# SCH_Snoopy_2026-08-06.net
KiCad netlist of a schematic drawn in EasyEDA
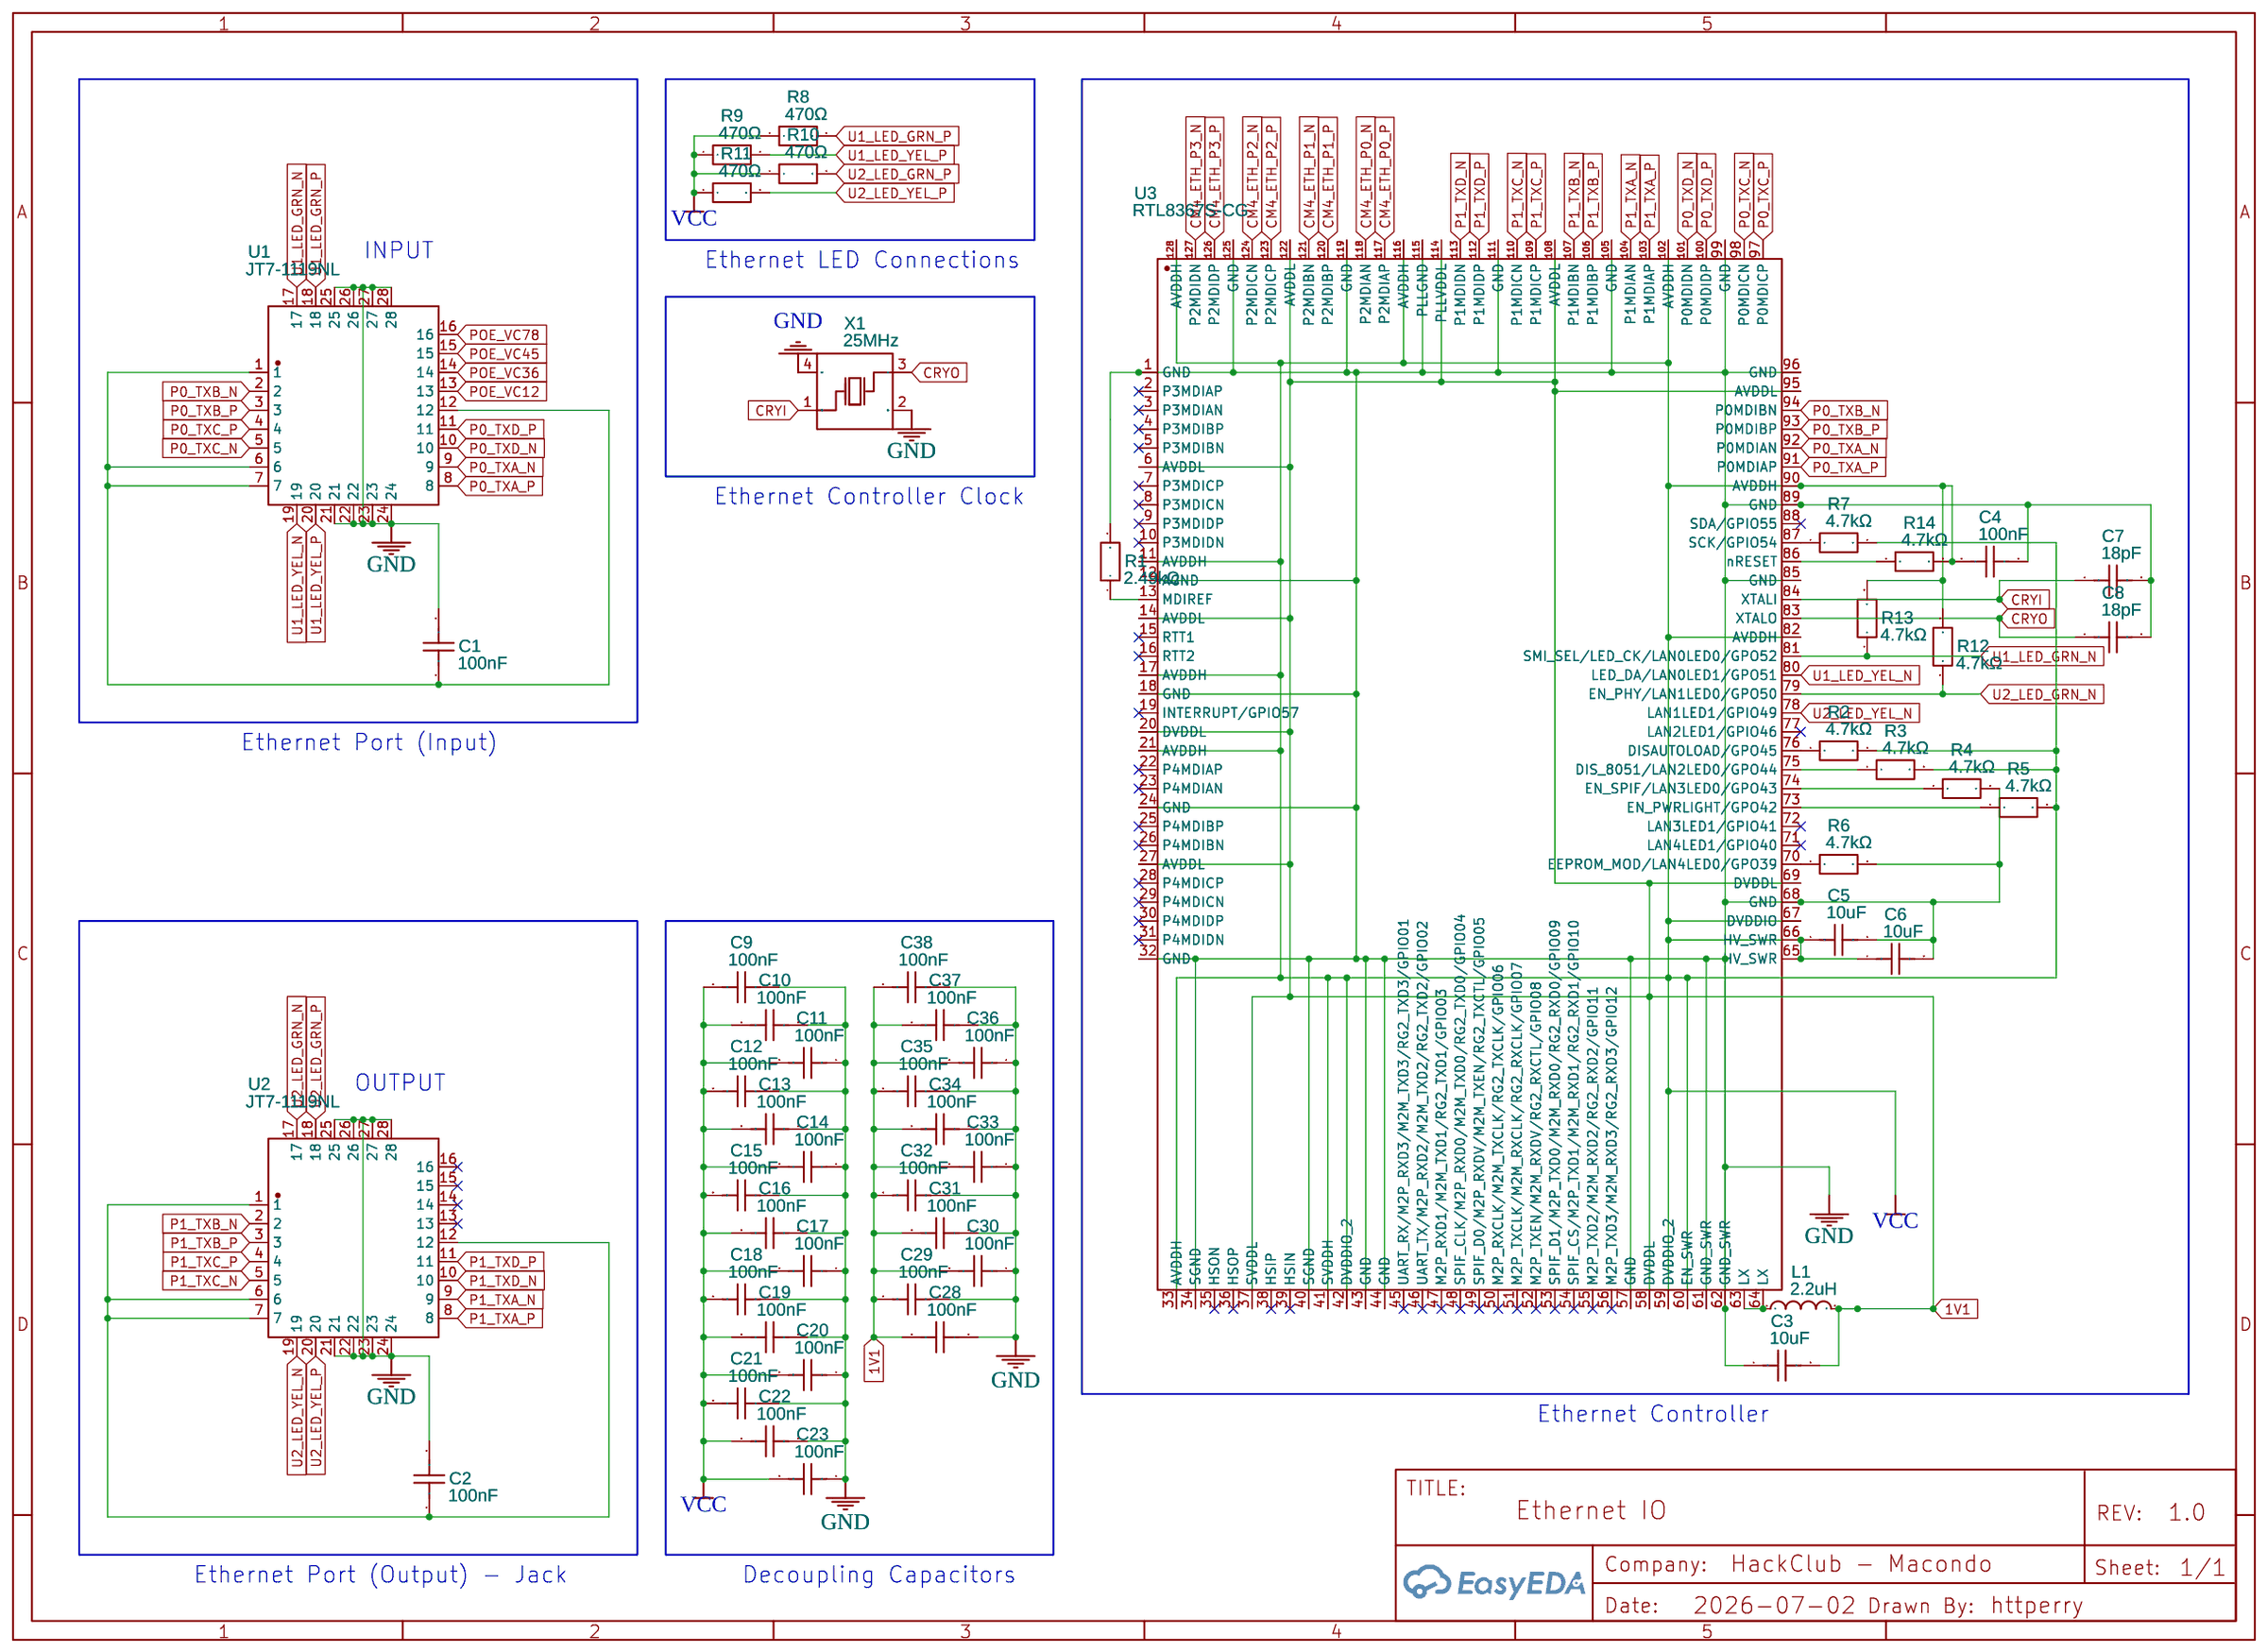
[diagram p0: Ethernet_IO]
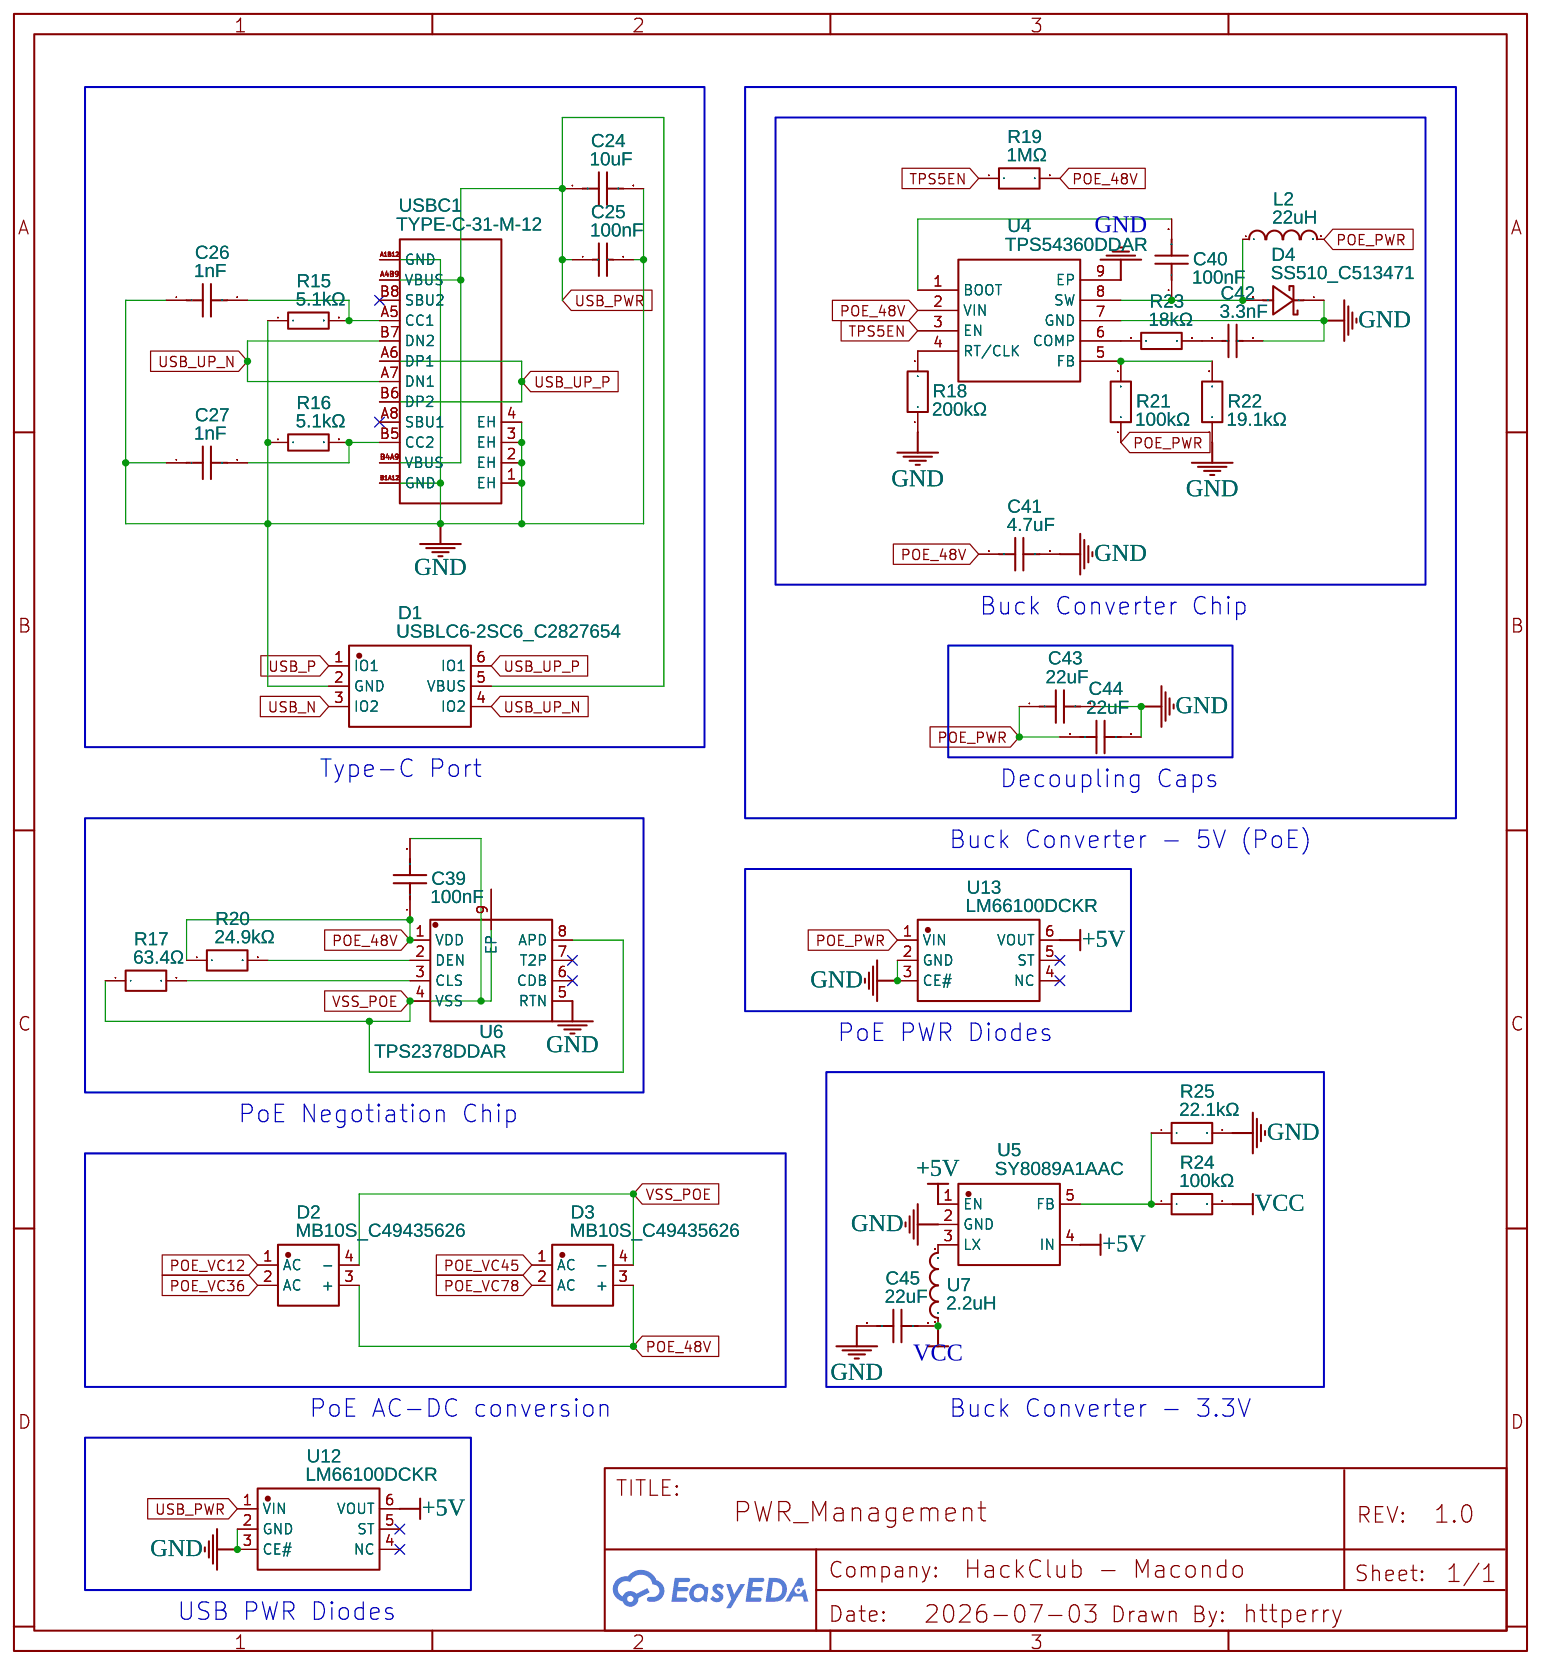
[diagram p1: PWR_Management]
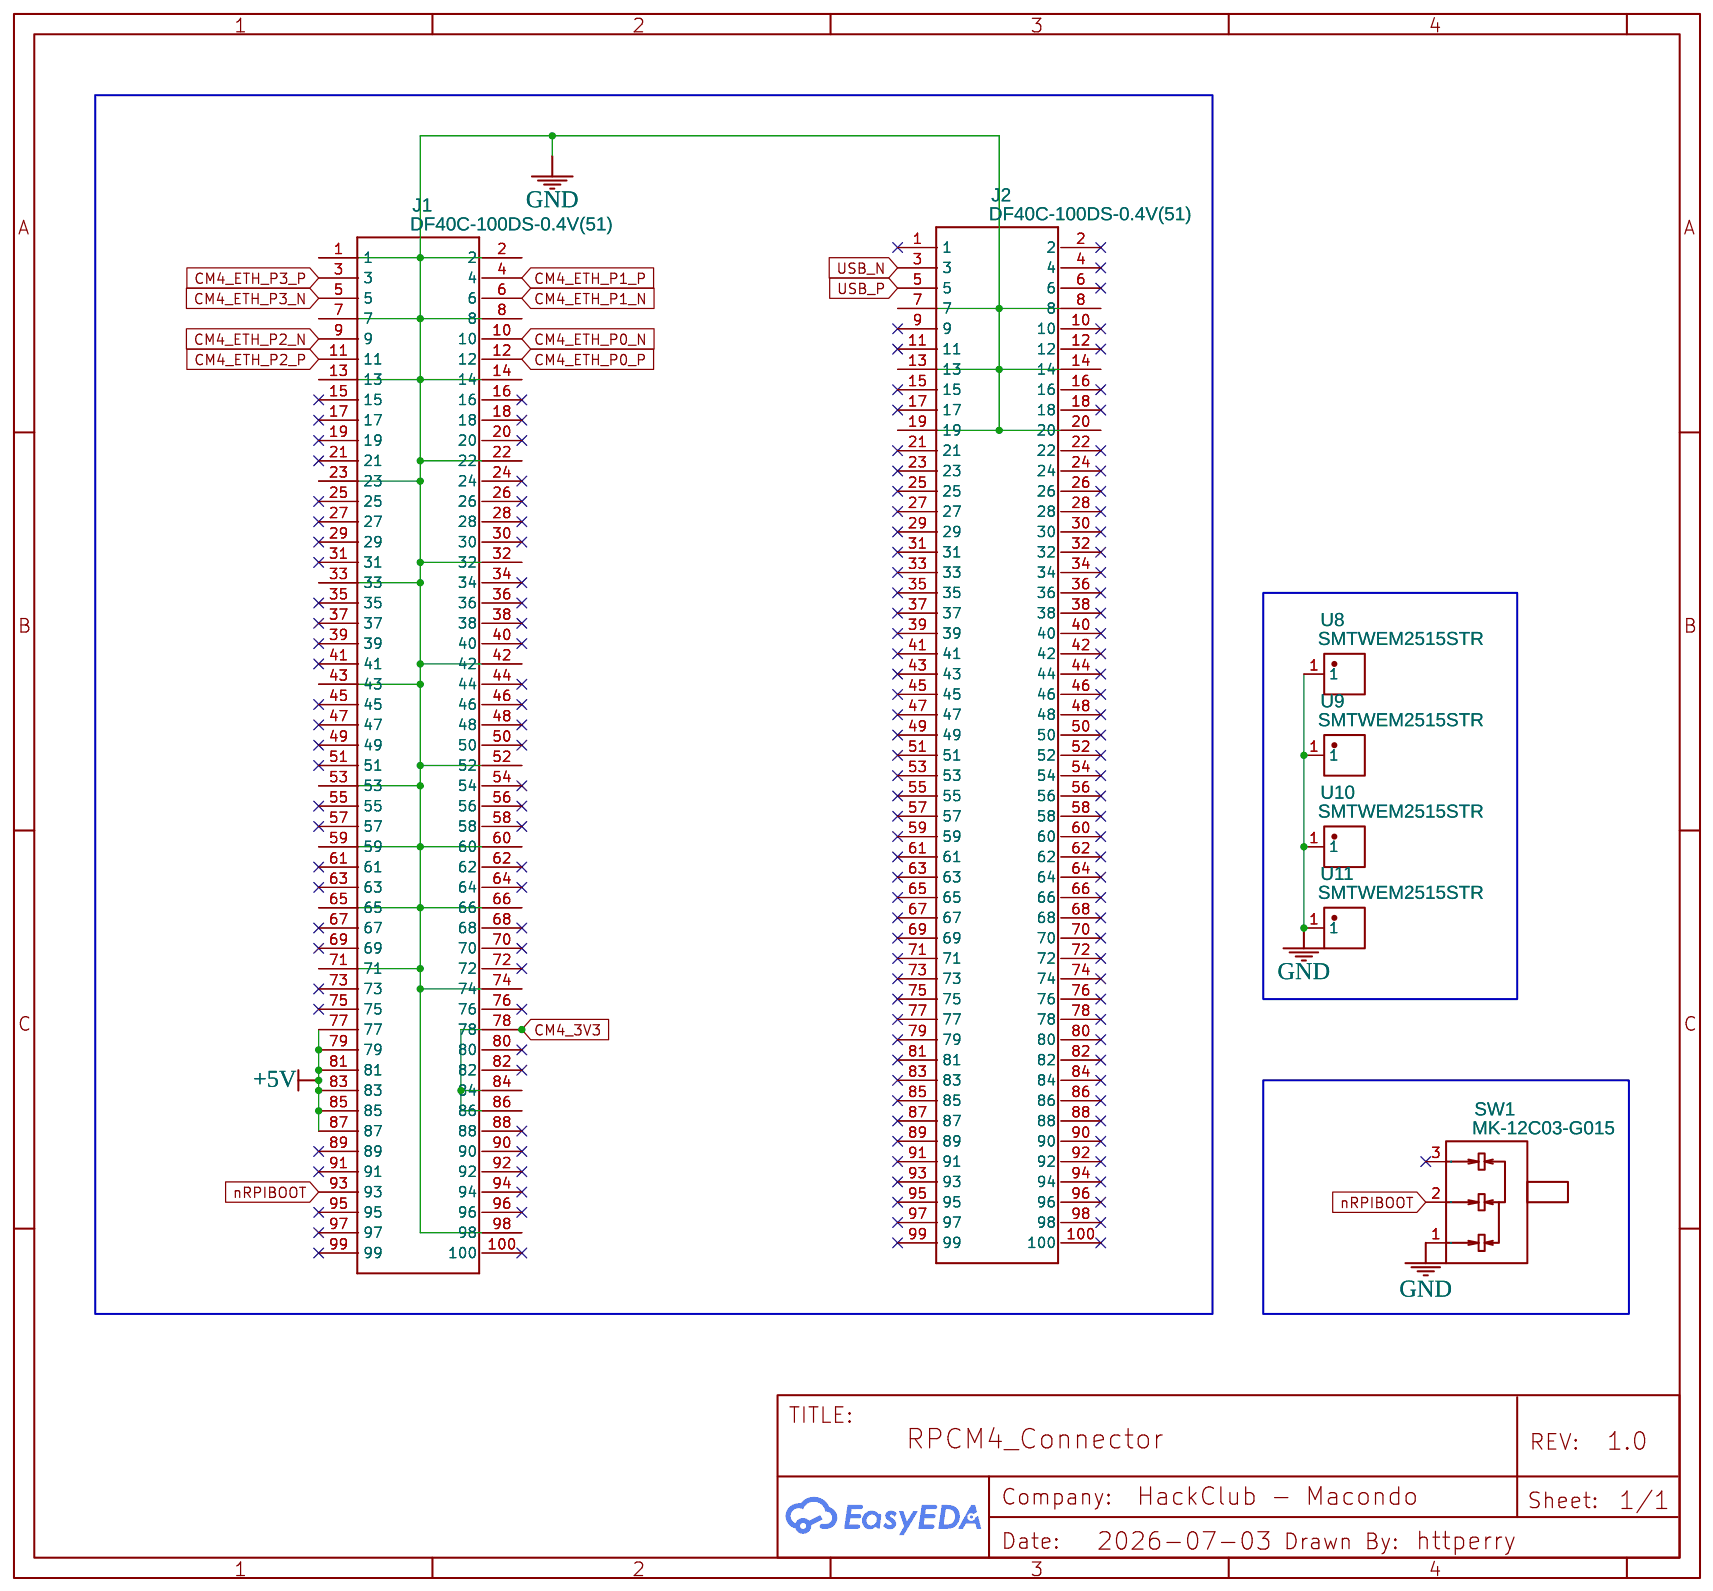
[diagram p2: RPCM4_Connector]

(export (version "E")
  (design (tool "Eeschema 10.0.6"))
  (components
    (comp (ref "C1")
      (value "100nF")
      (fields
        (field (name "Manufacturer Part") "AC0402KRX7R9BB104")
        (field (name "Manufacturer") "YAGEO(国巨)")
      )
      (libsource (lib "") (part "AC0402KRX7R9BB104_1"))
    )
    (comp (ref "C2")
      (value "100nF")
      (fields
        (field (name "Manufacturer Part") "AC0402KRX7R9BB104")
        (field (name "Manufacturer") "YAGEO(国巨)")
      )
      (libsource (lib "") (part "AC0402KRX7R9BB104_1"))
    )
    (comp (ref "C3")
      (value "10uF")
      (fields
        (field (name "Manufacturer Part") "HGC0603R5106M250NTHJ")
        (field (name "Manufacturer") "Chinocera(华瓷)")
      )
      (libsource (lib "") (part "HGC0603R5106M250NTHJ"))
    )
    (comp (ref "C4")
      (value "100nF")
      (fields
        (field (name "Manufacturer Part") "AC0402KRX7R9BB104")
        (field (name "Manufacturer") "YAGEO(国巨)")
      )
      (libsource (lib "") (part "AC0402KRX7R9BB104"))
    )
    (comp (ref "C5")
      (value "10uF")
      (fields
        (field (name "Manufacturer Part") "HGC0603R5106M250NTHJ")
        (field (name "Manufacturer") "Chinocera(华瓷)")
      )
      (libsource (lib "") (part "HGC0603R5106M250NTHJ"))
    )
    (comp (ref "C6")
      (value "10uF")
      (fields
        (field (name "Manufacturer Part") "HGC0603R5106M250NTHJ")
        (field (name "Manufacturer") "Chinocera(华瓷)")
      )
      (libsource (lib "") (part "HGC0603R5106M250NTHJ"))
    )
    (comp (ref "C7")
      (value "18pF")
      (fields
        (field (name "Manufacturer Part") "GRM1555C1H180JA01D")
        (field (name "Manufacturer") "muRata(村田)")
      )
      (libsource (lib "") (part "GRM1555C1H180JA01D"))
    )
    (comp (ref "C8")
      (value "18pF")
      (fields
        (field (name "Manufacturer Part") "GRM1555C1H180JA01D")
        (field (name "Manufacturer") "muRata(村田)")
      )
      (libsource (lib "") (part "GRM1555C1H180JA01D"))
    )
    (comp (ref "C9")
      (value "100nF")
      (fields
        (field (name "Manufacturer Part") "AC0402KRX7R9BB104")
        (field (name "Manufacturer") "YAGEO(国巨)")
      )
      (libsource (lib "") (part "AC0402KRX7R9BB104"))
    )
    (comp (ref "C10")
      (value "100nF")
      (fields
        (field (name "Manufacturer Part") "AC0402KRX7R9BB104")
        (field (name "Manufacturer") "YAGEO(国巨)")
      )
      (libsource (lib "") (part "AC0402KRX7R9BB104"))
    )
    (comp (ref "C11")
      (value "100nF")
      (fields
        (field (name "Manufacturer Part") "AC0402KRX7R9BB104")
        (field (name "Manufacturer") "YAGEO(国巨)")
      )
      (libsource (lib "") (part "AC0402KRX7R9BB104"))
    )
    (comp (ref "C12")
      (value "100nF")
      (fields
        (field (name "Manufacturer Part") "AC0402KRX7R9BB104")
        (field (name "Manufacturer") "YAGEO(国巨)")
      )
      (libsource (lib "") (part "AC0402KRX7R9BB104"))
    )
    (comp (ref "C13")
      (value "100nF")
      (fields
        (field (name "Manufacturer Part") "AC0402KRX7R9BB104")
        (field (name "Manufacturer") "YAGEO(国巨)")
      )
      (libsource (lib "") (part "AC0402KRX7R9BB104"))
    )
    (comp (ref "C14")
      (value "100nF")
      (fields
        (field (name "Manufacturer Part") "AC0402KRX7R9BB104")
        (field (name "Manufacturer") "YAGEO(国巨)")
      )
      (libsource (lib "") (part "AC0402KRX7R9BB104"))
    )
    (comp (ref "C15")
      (value "100nF")
      (fields
        (field (name "Manufacturer Part") "AC0402KRX7R9BB104")
        (field (name "Manufacturer") "YAGEO(国巨)")
      )
      (libsource (lib "") (part "AC0402KRX7R9BB104"))
    )
    (comp (ref "C16")
      (value "100nF")
      (fields
        (field (name "Manufacturer Part") "AC0402KRX7R9BB104")
        (field (name "Manufacturer") "YAGEO(国巨)")
      )
      (libsource (lib "") (part "AC0402KRX7R9BB104"))
    )
    (comp (ref "C17")
      (value "100nF")
      (fields
        (field (name "Manufacturer Part") "AC0402KRX7R9BB104")
        (field (name "Manufacturer") "YAGEO(国巨)")
      )
      (libsource (lib "") (part "AC0402KRX7R9BB104"))
    )
    (comp (ref "C18")
      (value "100nF")
      (fields
        (field (name "Manufacturer Part") "AC0402KRX7R9BB104")
        (field (name "Manufacturer") "YAGEO(国巨)")
      )
      (libsource (lib "") (part "AC0402KRX7R9BB104"))
    )
    (comp (ref "C19")
      (value "100nF")
      (fields
        (field (name "Manufacturer Part") "AC0402KRX7R9BB104")
        (field (name "Manufacturer") "YAGEO(国巨)")
      )
      (libsource (lib "") (part "AC0402KRX7R9BB104"))
    )
    (comp (ref "C20")
      (value "100nF")
      (fields
        (field (name "Manufacturer Part") "AC0402KRX7R9BB104")
        (field (name "Manufacturer") "YAGEO(国巨)")
      )
      (libsource (lib "") (part "AC0402KRX7R9BB104"))
    )
    (comp (ref "C21")
      (value "100nF")
      (fields
        (field (name "Manufacturer Part") "AC0402KRX7R9BB104")
        (field (name "Manufacturer") "YAGEO(国巨)")
      )
      (libsource (lib "") (part "AC0402KRX7R9BB104"))
    )
    (comp (ref "C22")
      (value "100nF")
      (fields
        (field (name "Manufacturer Part") "AC0402KRX7R9BB104")
        (field (name "Manufacturer") "YAGEO(国巨)")
      )
      (libsource (lib "") (part "AC0402KRX7R9BB104"))
    )
    (comp (ref "C23")
      (value "100nF")
      (fields
        (field (name "Manufacturer Part") "AC0402KRX7R9BB104")
        (field (name "Manufacturer") "YAGEO(国巨)")
      )
      (libsource (lib "") (part "AC0402KRX7R9BB104"))
    )
    (comp (ref "C28")
      (value "100nF")
      (fields
        (field (name "Manufacturer Part") "AC0402KRX7R9BB104")
        (field (name "Manufacturer") "YAGEO(国巨)")
      )
      (libsource (lib "") (part "AC0402KRX7R9BB104"))
    )
    (comp (ref "C29")
      (value "100nF")
      (fields
        (field (name "Manufacturer Part") "AC0402KRX7R9BB104")
        (field (name "Manufacturer") "YAGEO(国巨)")
      )
      (libsource (lib "") (part "AC0402KRX7R9BB104"))
    )
    (comp (ref "C30")
      (value "100nF")
      (fields
        (field (name "Manufacturer Part") "AC0402KRX7R9BB104")
        (field (name "Manufacturer") "YAGEO(国巨)")
      )
      (libsource (lib "") (part "AC0402KRX7R9BB104"))
    )
    (comp (ref "C31")
      (value "100nF")
      (fields
        (field (name "Manufacturer Part") "AC0402KRX7R9BB104")
        (field (name "Manufacturer") "YAGEO(国巨)")
      )
      (libsource (lib "") (part "AC0402KRX7R9BB104"))
    )
    (comp (ref "C32")
      (value "100nF")
      (fields
        (field (name "Manufacturer Part") "AC0402KRX7R9BB104")
        (field (name "Manufacturer") "YAGEO(国巨)")
      )
      (libsource (lib "") (part "AC0402KRX7R9BB104"))
    )
    (comp (ref "C33")
      (value "100nF")
      (fields
        (field (name "Manufacturer Part") "AC0402KRX7R9BB104")
        (field (name "Manufacturer") "YAGEO(国巨)")
      )
      (libsource (lib "") (part "AC0402KRX7R9BB104"))
    )
    (comp (ref "C34")
      (value "100nF")
      (fields
        (field (name "Manufacturer Part") "AC0402KRX7R9BB104")
        (field (name "Manufacturer") "YAGEO(国巨)")
      )
      (libsource (lib "") (part "AC0402KRX7R9BB104"))
    )
    (comp (ref "C35")
      (value "100nF")
      (fields
        (field (name "Manufacturer Part") "AC0402KRX7R9BB104")
        (field (name "Manufacturer") "YAGEO(国巨)")
      )
      (libsource (lib "") (part "AC0402KRX7R9BB104"))
    )
    (comp (ref "C36")
      (value "100nF")
      (fields
        (field (name "Manufacturer Part") "AC0402KRX7R9BB104")
        (field (name "Manufacturer") "YAGEO(国巨)")
      )
      (libsource (lib "") (part "AC0402KRX7R9BB104"))
    )
    (comp (ref "C37")
      (value "100nF")
      (fields
        (field (name "Manufacturer Part") "AC0402KRX7R9BB104")
        (field (name "Manufacturer") "YAGEO(国巨)")
      )
      (libsource (lib "") (part "AC0402KRX7R9BB104"))
    )
    (comp (ref "C38")
      (value "100nF")
      (fields
        (field (name "Manufacturer Part") "AC0402KRX7R9BB104")
        (field (name "Manufacturer") "YAGEO(国巨)")
      )
      (libsource (lib "") (part "AC0402KRX7R9BB104"))
    )
    (comp (ref "L1")
      (value "2.2uH")
      (fields (field (name "Manufacturer Part") "ZEMS160865-2R2M") (field (name "Manufacturer") "ZE(增益)"))
      (libsource (lib "") (part "ZEMS160865-2R2M"))
    )
    (comp (ref "R1")
      (value "2.49kΩ")
      (fields (field (name "Manufacturer Part") "FRC0402F2491TS") (field (name "Manufacturer") "FOJAN(富捷)"))
      (libsource (lib "") (part "FRC0402F2491TS"))
    )
    (comp (ref "R2")
      (value "4.7kΩ")
      (fields
        (field (name "Manufacturer Part") "CRCW04024K70FKED")
        (field (name "Manufacturer") "VISHAY(威世)")
      )
      (libsource (lib "") (part "CRCW04024K70FKED_1"))
    )
    (comp (ref "R3")
      (value "4.7kΩ")
      (fields
        (field (name "Manufacturer Part") "CRCW04024K70FKED")
        (field (name "Manufacturer") "VISHAY(威世)")
      )
      (libsource (lib "") (part "CRCW04024K70FKED_1"))
    )
    (comp (ref "R4")
      (value "4.7kΩ")
      (fields
        (field (name "Manufacturer Part") "CRCW04024K70FKED")
        (field (name "Manufacturer") "VISHAY(威世)")
      )
      (libsource (lib "") (part "CRCW04024K70FKED_1"))
    )
    (comp (ref "R5")
      (value "4.7kΩ")
      (fields
        (field (name "Manufacturer Part") "CRCW04024K70FKED")
        (field (name "Manufacturer") "VISHAY(威世)")
      )
      (libsource (lib "") (part "CRCW04024K70FKED_1"))
    )
    (comp (ref "R6")
      (value "4.7kΩ")
      (fields
        (field (name "Manufacturer Part") "CRCW04024K70FKED")
        (field (name "Manufacturer") "VISHAY(威世)")
      )
      (libsource (lib "") (part "CRCW04024K70FKED_1"))
    )
    (comp (ref "R7")
      (value "4.7kΩ")
      (fields
        (field (name "Manufacturer Part") "CRCW04024K70FKED")
        (field (name "Manufacturer") "VISHAY(威世)")
      )
      (libsource (lib "") (part "CRCW04024K70FKED_1"))
    )
    (comp (ref "R8")
      (value "470Ω")
      (fields (field (name "Manufacturer Part") "FRC0402F4700TS") (field (name "Manufacturer") "FOJAN(富捷)"))
      (libsource (lib "") (part "FRC0402F4700TS"))
    )
    (comp (ref "R9")
      (value "470Ω")
      (fields (field (name "Manufacturer Part") "FRC0402F4700TS") (field (name "Manufacturer") "FOJAN(富捷)"))
      (libsource (lib "") (part "FRC0402F4700TS"))
    )
    (comp (ref "R10")
      (value "470Ω")
      (fields (field (name "Manufacturer Part") "FRC0402F4700TS") (field (name "Manufacturer") "FOJAN(富捷)"))
      (libsource (lib "") (part "FRC0402F4700TS"))
    )
    (comp (ref "R11")
      (value "470Ω")
      (fields (field (name "Manufacturer Part") "FRC0402F4700TS") (field (name "Manufacturer") "FOJAN(富捷)"))
      (libsource (lib "") (part "FRC0402F4700TS"))
    )
    (comp (ref "R12")
      (value "4.7kΩ")
      (fields
        (field (name "Manufacturer Part") "CRCW04024K70FKED")
        (field (name "Manufacturer") "VISHAY(威世)")
      )
      (libsource (lib "") (part "CRCW04024K70FKED"))
    )
    (comp (ref "R13")
      (value "4.7kΩ")
      (fields
        (field (name "Manufacturer Part") "CRCW04024K70FKED")
        (field (name "Manufacturer") "VISHAY(威世)")
      )
      (libsource (lib "") (part "CRCW04024K70FKED"))
    )
    (comp (ref "R14")
      (value "4.7kΩ")
      (fields
        (field (name "Manufacturer Part") "CRCW04024K70FKED")
        (field (name "Manufacturer") "VISHAY(威世)")
      )
      (libsource (lib "") (part "CRCW04024K70FKED_1"))
    )
    (comp (ref "U1")
      (value "JT7-1119NL")
      (fields (field (name "Manufacturer") "PULSE(普思)"))
      (libsource (lib "") (part "JT7-1119NL"))
    )
    (comp (ref "U2")
      (value "JT7-1119NL")
      (fields (field (name "Manufacturer") "PULSE(普思)"))
      (libsource (lib "") (part "JT7-1119NL"))
    )
    (comp (ref "U3")
      (value "RTL8367S-CG")
      (fields (field (name "Manufacturer") "REALTEK(瑞昱)"))
      (libsource (lib "") (part "RTL8367S-CG"))
    )
    (comp (ref "X1")
      (value "25MHz")
      (fields (field (name "Manufacturer Part") "TAXM25M4RLBCCT2T") (field (name "Manufacturer") "YJX(雅晶鑫)"))
      (libsource (lib "") (part "SMD-3225_4P25MHZ20PF10PPM-40&#126;+85℃"))
    )
    (comp (ref "C24")
      (value "10uF")
      (fields
        (field (name "Manufacturer Part") "HGC0603R5106M250NTHJ")
        (field (name "Manufacturer") "Chinocera(华瓷)")
      )
      (libsource (lib "") (part "HGC0603R5106M250NTHJ"))
    )
    (comp (ref "C25")
      (value "100nF")
      (fields
        (field (name "Manufacturer Part") "CC0402KRX5R8BB104")
        (field (name "Manufacturer") "YAGEO(国巨)")
      )
      (libsource (lib "") (part "CC0402KRX5R8BB104"))
    )
    (comp (ref "C26")
      (value "1nF")
      (fields
        (field (name "Manufacturer Part") "CC0402KRX7R8BB102")
        (field (name "Manufacturer") "YAGEO(国巨)")
      )
      (libsource (lib "") (part "CC0402KRX7R8BB102"))
    )
    (comp (ref "C27")
      (value "1nF")
      (fields
        (field (name "Manufacturer Part") "CC0402KRX7R8BB102")
        (field (name "Manufacturer") "YAGEO(国巨)")
      )
      (libsource (lib "") (part "CC0402KRX7R8BB102"))
    )
    (comp (ref "C39")
      (value "100nF")
      (fields
        (field (name "Manufacturer Part") "GCJ188R72A104KA01D")
        (field (name "Manufacturer") "muRata(村田)")
      )
      (libsource (lib "") (part "GCJ188R72A104KA01D"))
    )
    (comp (ref "C40")
      (value "100nF")
      (fields
        (field (name "Manufacturer Part") "GCJ188R72A104KA01D")
        (field (name "Manufacturer") "muRata(村田)")
      )
      (libsource (lib "") (part "GCJ188R72A104KA01D"))
    )
    (comp (ref "C41")
      (value "4.7uF")
      (fields
        (field (name "Manufacturer Part") "GRM31CC72A475KE11L")
        (field (name "Manufacturer") "muRata(村田)")
      )
      (libsource (lib "") (part "GRM31CC72A475KE11L"))
    )
    (comp (ref "C42")
      (value "3.3nF")
      (fields
        (field (name "Manufacturer Part") "CC0402KRX7R9BB332")
        (field (name "Manufacturer") "YAGEO(国巨)")
      )
      (libsource (lib "") (part "CC0402KRX7R9BB332"))
    )
    (comp (ref "C43")
      (value "22uF")
      (fields
        (field (name "Manufacturer Part") "CL10A226MP8NUNE")
        (field (name "Manufacturer") "SAMSUNG(三星)")
      )
      (libsource (lib "") (part "CL10A226MP8NUNE"))
    )
    (comp (ref "C44")
      (value "22uF")
      (fields
        (field (name "Manufacturer Part") "CL10A226MP8NUNE")
        (field (name "Manufacturer") "SAMSUNG(三星)")
      )
      (libsource (lib "") (part "CL10A226MP8NUNE"))
    )
    (comp (ref "C45")
      (value "22uF")
      (fields
        (field (name "Manufacturer Part") "HGC0402R5226M100NTEJ")
        (field (name "Manufacturer") "Chinocera(华瓷)")
      )
      (libsource (lib "") (part "HGC0402R5226M100NTEJ"))
    )
    (comp (ref "D1")
      (value "USBLC6-2SC6_C2827654")
      (fields
        (field (name "Manufacturer Part") "USBLC6-2SC6")
        (field (name "Manufacturer") "TECH PUBLIC(台舟)")
      )
      (libsource (lib "") (part "USBLC6-2SC6_C2827654"))
    )
    (comp (ref "D2")
      (value "MB10S_C49435626")
      (fields (field (name "Manufacturer Part") "MB10S") (field (name "Manufacturer") "Huixin(慧芯)"))
      (libsource (lib "") (part "MB10S_C49435626"))
    )
    (comp (ref "D3")
      (value "MB10S_C49435626")
      (fields (field (name "Manufacturer Part") "MB10S") (field (name "Manufacturer") "Huixin(慧芯)"))
      (libsource (lib "") (part "MB10S_C49435626"))
    )
    (comp (ref "D4")
      (value "SS510_C513471")
      (fields (field (name "Manufacturer Part") "SS510") (field (name "Manufacturer") "Slkor(萨科微)"))
      (libsource (lib "") (part "SS510_C513471"))
    )
    (comp (ref "L2")
      (value "22uH")
      (fields
        (field (name "Manufacturer Part") "YSPI0630A-220M")
        (field (name "Manufacturer") "YJYCOIN(益嘉源)")
      )
      (libsource (lib "") (part "YSPI0630A-220M"))
    )
    (comp (ref "R15")
      (value "5.1kΩ")
      (fields (field (name "Manufacturer Part") "RMC06035.1K5%N") (field (name "Manufacturer") "Tyohm(幸亚电阻)"))
      (libsource (lib "") (part "RMC06035.1K5%N"))
    )
    (comp (ref "R16")
      (value "5.1kΩ")
      (fields (field (name "Manufacturer Part") "RMC06035.1K5%N") (field (name "Manufacturer") "Tyohm(幸亚电阻)"))
      (libsource (lib "") (part "RMC06035.1K5%N"))
    )
    (comp (ref "R17")
      (value "63.4Ω")
      (fields (field (name "Manufacturer Part") "PTFR0603B63R4P9") (field (name "Manufacturer") "RESI(开步睿思)"))
      (libsource (lib "") (part "PTFR0603B63R4P9"))
    )
    (comp (ref "R18")
      (value "200kΩ")
      (fields (field (name "Manufacturer Part") "ARG02BTC2003") (field (name "Manufacturer") "Viking(光颉)"))
      (libsource (lib "") (part "ARG02BTC2003"))
    )
    (comp (ref "R19")
      (value "1MΩ")
      (fields (field (name "Manufacturer Part") "AR05BTC1004") (field (name "Manufacturer") "Viking(光颉)"))
      (libsource (lib "") (part "AR05BTC1004"))
    )
    (comp (ref "R20")
      (value "24.9kΩ")
      (fields (field (name "Manufacturer Part") "PTFR0603B24K9N9") (field (name "Manufacturer") "RESI(开步睿思)"))
      (libsource (lib "") (part "PTFR0603B24K9N9"))
    )
    (comp (ref "R21")
      (value "100kΩ")
      (fields (field (name "Manufacturer Part") "RT0402BRD07100KL") (field (name "Manufacturer") "YAGEO(国巨)"))
      (libsource (lib "") (part "RT0402BRD07100KL_1"))
    )
    (comp (ref "R22")
      (value "19.1kΩ")
      (fields (field (name "Manufacturer Part") "FRC0402F1912TS") (field (name "Manufacturer") "FOJAN(富捷)"))
      (libsource (lib "") (part "FRC0402F1912TS"))
    )
    (comp (ref "R23")
      (value "18kΩ")
      (fields (field (name "Manufacturer Part") "AECR0402F18K0K9") (field (name "Manufacturer") "RESI(开步睿思)"))
      (libsource (lib "") (part "AECR0402F18K0K9"))
    )
    (comp (ref "R24")
      (value "100kΩ")
      (fields (field (name "Manufacturer Part") "RT0402BRD07100KL") (field (name "Manufacturer") "YAGEO(国巨)"))
      (libsource (lib "") (part "RT0402BRD07100KL"))
    )
    (comp (ref "R25")
      (value "22.1kΩ")
      (fields
        (field (name "Manufacturer Part") "CRCW040222K1FKED")
        (field (name "Manufacturer") "VISHAY(威世)")
      )
      (libsource (lib "") (part "CRCW040222K1FKED"))
    )
    (comp (ref "U4")
      (value "TPS54360DDAR")
      (fields (field (name "Manufacturer") "TI(德州仪器)"))
      (libsource (lib "") (part "TPS54360DDAR"))
    )
    (comp (ref "U5")
      (value "SY8089A1AAC")
      (fields (field (name "Manufacturer") "Silergy(矽力杰)"))
      (libsource (lib "") (part "SY8089A1AAC"))
    )
    (comp (ref "U6")
      (value "TPS2378DDAR")
      (fields (field (name "Manufacturer") "TI(德州仪器)"))
      (libsource (lib "") (part "TPS2378DDAR"))
    )
    (comp (ref "U7")
      (value "2.2uH")
      (fields
        (field (name "Manufacturer Part") "FTC201610S2R2MBCA")
        (field (name "Manufacturer") "cjiang(长江微电)")
      )
      (libsource (lib "") (part "FTC201610S2R2MBCA"))
    )
    (comp (ref "U12")
      (value "LM66100DCKR")
      (fields (field (name "Manufacturer") "TI(德州仪器)"))
      (libsource (lib "") (part "LM66100DCKR"))
    )
    (comp (ref "U13")
      (value "LM66100DCKR")
      (fields (field (name "Manufacturer") "TI(德州仪器)"))
      (libsource (lib "") (part "LM66100DCKR"))
    )
    (comp (ref "USBC1")
      (value "TYPE-C-31-M-12")
      (fields (field (name "Manufacturer") "韩国韩荣"))
      (libsource (lib "") (part "TYPE-C-31-M-12"))
    )
    (comp (ref "J1")
      (value "DF40C-100DS-0.4V(51)")
      (fields (field (name "Manufacturer") "HRS(广濑)"))
      (libsource (lib "") (part "DF40C-100DS-0.4V(51)"))
    )
    (comp (ref "J2")
      (value "DF40C-100DS-0.4V(51)")
      (fields (field (name "Manufacturer") "HRS(广濑)"))
      (libsource (lib "") (part "DF40C-100DS-0.4V(51)"))
    )
    (comp (ref "SW1")
      (value "MK-12C03-G015")
      (fields (field (name "Manufacturer") "G-Switch(品赞)"))
      (libsource (lib "") (part "MK-12C03-G015"))
    )
    (comp (ref "U8")
      (value "SMTWEM2515STR")
      (fields (field (name "Manufacturer") "YIYUAN(怡远)"))
      (libsource (lib "") (part "SMTWEM2515STR"))
    )
    (comp (ref "U9")
      (value "SMTWEM2515STR")
      (fields (field (name "Manufacturer") "YIYUAN(怡远)"))
      (libsource (lib "") (part "SMTWEM2515STR"))
    )
    (comp (ref "U10")
      (value "SMTWEM2515STR")
      (fields (field (name "Manufacturer") "YIYUAN(怡远)"))
      (libsource (lib "") (part "SMTWEM2515STR"))
    )
    (comp (ref "U11")
      (value "SMTWEM2515STR")
      (fields (field (name "Manufacturer") "YIYUAN(怡远)"))
      (libsource (lib "") (part "SMTWEM2515STR"))
    )
  )
  (nets
    (net (code "1") (name "+5V") (class "Default")
      (node (ref "J1") (pin "77") (pinfunction "77_77") (pintype "bidirectional"))
      (node (ref "J1") (pin "79") (pinfunction "79_79") (pintype "bidirectional"))
      (node (ref "J1") (pin "81") (pinfunction "81_81") (pintype "bidirectional"))
      (node (ref "J1") (pin "83") (pinfunction "83_83") (pintype "bidirectional"))
      (node (ref "J1") (pin "85") (pinfunction "85_85") (pintype "bidirectional"))
      (node (ref "J1") (pin "87") (pinfunction "87_87") (pintype "bidirectional"))
      (node (ref "U12") (pin "6") (pinfunction "VOUT_6") (pintype "unspecified"))
      (node (ref "U13") (pin "6") (pinfunction "VOUT_6") (pintype "unspecified"))
      (node (ref "U5") (pin "1") (pinfunction "EN_1") (pintype "unspecified"))
      (node (ref "U5") (pin "4") (pinfunction "IN_4") (pintype "unspecified"))
    )
    (net (code "2") (name "1V1") (class "Default")
      (node (ref "C28") (pin "2") (pinfunction "2_2") (pintype "unspecified"))
      (node (ref "C29") (pin "2") (pinfunction "2_2") (pintype "unspecified"))
      (node (ref "C3") (pin "2") (pinfunction "2_2") (pintype "unspecified"))
      (node (ref "C30") (pin "2") (pinfunction "2_2") (pintype "unspecified"))
      (node (ref "C31") (pin "2") (pinfunction "2_2") (pintype "unspecified"))
      (node (ref "C32") (pin "2") (pinfunction "2_2") (pintype "unspecified"))
      (node (ref "C33") (pin "2") (pinfunction "2_2") (pintype "unspecified"))
      (node (ref "C34") (pin "2") (pinfunction "2_2") (pintype "unspecified"))
      (node (ref "C35") (pin "2") (pinfunction "2_2") (pintype "unspecified"))
      (node (ref "C36") (pin "2") (pinfunction "2_2") (pintype "unspecified"))
      (node (ref "C37") (pin "2") (pinfunction "2_2") (pintype "unspecified"))
      (node (ref "C38") (pin "2") (pinfunction "2_2") (pintype "unspecified"))
      (node (ref "L1") (pin "2") (pinfunction "2_2") (pintype "unspecified"))
      (node (ref "U3") (pin "108") (pinfunction "AVDDL_108") (pintype "unspecified"))
      (node (ref "U3") (pin "114") (pinfunction "PLLVDDL_114") (pintype "unspecified"))
      (node (ref "U3") (pin "122") (pinfunction "AVDDL_122") (pintype "unspecified"))
      (node (ref "U3") (pin "14") (pinfunction "AVDDL_14") (pintype "unspecified"))
      (node (ref "U3") (pin "20") (pinfunction "DVDDL_20") (pintype "unspecified"))
      (node (ref "U3") (pin "27") (pinfunction "AVDDL_27") (pintype "unspecified"))
      (node (ref "U3") (pin "37") (pinfunction "SVDDL_37") (pintype "unspecified"))
      (node (ref "U3") (pin "58") (pinfunction "DVDDL_58") (pintype "unspecified"))
      (node (ref "U3") (pin "6") (pinfunction "AVDDL_6") (pintype "unspecified"))
      (node (ref "U3") (pin "69") (pinfunction "DVDDL_69") (pintype "unspecified"))
      (node (ref "U3") (pin "95") (pinfunction "AVDDL_95") (pintype "unspecified"))
    )
    (net (code "3") (name "CM4_3V3") (class "Default")
      (node (ref "J1") (pin "78") (pinfunction "78_78") (pintype "bidirectional"))
      (node (ref "J1") (pin "84") (pinfunction "84_84") (pintype "bidirectional"))
      (node (ref "J1") (pin "86") (pinfunction "86_86") (pintype "bidirectional"))
    )
    (net (code "4") (name "CM4_ETH_P0_N") (class "Default")
      (node (ref "J1") (pin "10") (pinfunction "10_10") (pintype "bidirectional"))
      (node (ref "U3") (pin "118") (pinfunction "P2MDIAN_118") (pintype "unspecified"))
    )
    (net (code "5") (name "CM4_ETH_P0_P") (class "Default")
      (node (ref "J1") (pin "12") (pinfunction "12_12") (pintype "bidirectional"))
      (node (ref "U3") (pin "117") (pinfunction "P2MDIAP_117") (pintype "unspecified"))
    )
    (net (code "6") (name "CM4_ETH_P1_N") (class "Default")
      (node (ref "J1") (pin "6") (pinfunction "6_6") (pintype "bidirectional"))
      (node (ref "U3") (pin "121") (pinfunction "P2MDIBN_121") (pintype "unspecified"))
    )
    (net (code "7") (name "CM4_ETH_P1_P") (class "Default")
      (node (ref "J1") (pin "4") (pinfunction "4_4") (pintype "bidirectional"))
      (node (ref "U3") (pin "120") (pinfunction "P2MDIBP_120") (pintype "unspecified"))
    )
    (net (code "8") (name "CM4_ETH_P2_N") (class "Default")
      (node (ref "J1") (pin "9") (pinfunction "9_9") (pintype "bidirectional"))
      (node (ref "U3") (pin "124") (pinfunction "P2MDICN_124") (pintype "unspecified"))
    )
    (net (code "9") (name "CM4_ETH_P2_P") (class "Default")
      (node (ref "J1") (pin "11") (pinfunction "11_11") (pintype "bidirectional"))
      (node (ref "U3") (pin "123") (pinfunction "P2MDICP_123") (pintype "unspecified"))
    )
    (net (code "10") (name "CM4_ETH_P3_N") (class "Default")
      (node (ref "J1") (pin "5") (pinfunction "5_5") (pintype "bidirectional"))
      (node (ref "U3") (pin "127") (pinfunction "P2MDIDN_127") (pintype "unspecified"))
    )
    (net (code "11") (name "CM4_ETH_P3_P") (class "Default")
      (node (ref "J1") (pin "3") (pinfunction "3_3") (pintype "bidirectional"))
      (node (ref "U3") (pin "126") (pinfunction "P2MDIDP_126") (pintype "unspecified"))
    )
    (net (code "12") (name "CRYI") (class "Default")
      (node (ref "C7") (pin "1") (pinfunction "1_1") (pintype "unspecified"))
      (node (ref "U3") (pin "84") (pinfunction "XTALI_84") (pintype "unspecified"))
      (node (ref "X1") (pin "1") (pinfunction "OSC1_1") (pintype "unspecified"))
    )
    (net (code "13") (name "CRYO") (class "Default")
      (node (ref "C8") (pin "1") (pinfunction "1_1") (pintype "unspecified"))
      (node (ref "U3") (pin "83") (pinfunction "XTALO_83") (pintype "unspecified"))
      (node (ref "X1") (pin "3") (pinfunction "OSC2_3") (pintype "unspecified"))
    )
    (net (code "14") (name "GND") (class "Default")
      (node (ref "C1") (pin "2") (pinfunction "2_2") (pintype "unspecified"))
      (node (ref "C10") (pin "1") (pinfunction "1_1") (pintype "unspecified"))
      (node (ref "C11") (pin "1") (pinfunction "1_1") (pintype "unspecified"))
      (node (ref "C12") (pin "1") (pinfunction "1_1") (pintype "unspecified"))
      (node (ref "C13") (pin "1") (pinfunction "1_1") (pintype "unspecified"))
      (node (ref "C14") (pin "1") (pinfunction "1_1") (pintype "unspecified"))
      (node (ref "C15") (pin "1") (pinfunction "1_1") (pintype "unspecified"))
      (node (ref "C16") (pin "1") (pinfunction "1_1") (pintype "unspecified"))
      (node (ref "C17") (pin "1") (pinfunction "1_1") (pintype "unspecified"))
      (node (ref "C18") (pin "1") (pinfunction "1_1") (pintype "unspecified"))
      (node (ref "C19") (pin "1") (pinfunction "1_1") (pintype "unspecified"))
      (node (ref "C2") (pin "2") (pinfunction "2_2") (pintype "unspecified"))
      (node (ref "C20") (pin "1") (pinfunction "1_1") (pintype "unspecified"))
      (node (ref "C21") (pin "1") (pinfunction "1_1") (pintype "unspecified"))
      (node (ref "C22") (pin "1") (pinfunction "1_1") (pintype "unspecified"))
      (node (ref "C23") (pin "1") (pinfunction "1_1") (pintype "unspecified"))
      (node (ref "C24") (pin "2") (pinfunction "2_2") (pintype "unspecified"))
      (node (ref "C25") (pin "2") (pinfunction "2_2") (pintype "input"))
      (node (ref "C26") (pin "1") (pinfunction "1_1") (pintype "unspecified"))
      (node (ref "C27") (pin "1") (pinfunction "1_1") (pintype "unspecified"))
      (node (ref "C28") (pin "1") (pinfunction "1_1") (pintype "unspecified"))
      (node (ref "C29") (pin "1") (pinfunction "1_1") (pintype "unspecified"))
      (node (ref "C3") (pin "1") (pinfunction "1_1") (pintype "unspecified"))
      (node (ref "C30") (pin "1") (pinfunction "1_1") (pintype "unspecified"))
      (node (ref "C31") (pin "1") (pinfunction "1_1") (pintype "unspecified"))
      (node (ref "C32") (pin "1") (pinfunction "1_1") (pintype "unspecified"))
      (node (ref "C33") (pin "1") (pinfunction "1_1") (pintype "unspecified"))
      (node (ref "C34") (pin "1") (pinfunction "1_1") (pintype "unspecified"))
      (node (ref "C35") (pin "1") (pinfunction "1_1") (pintype "unspecified"))
      (node (ref "C36") (pin "1") (pinfunction "1_1") (pintype "unspecified"))
      (node (ref "C37") (pin "1") (pinfunction "1_1") (pintype "unspecified"))
      (node (ref "C38") (pin "1") (pinfunction "1_1") (pintype "unspecified"))
      (node (ref "C4") (pin "1") (pinfunction "1_1") (pintype "unspecified"))
      (node (ref "C41") (pin "2") (pinfunction "2_2") (pintype "unspecified"))
      (node (ref "C42") (pin "2") (pinfunction "2_2") (pintype "input"))
      (node (ref "C43") (pin "2") (pinfunction "2_2") (pintype "unspecified"))
      (node (ref "C44") (pin "2") (pinfunction "2_2") (pintype "unspecified"))
      (node (ref "C45") (pin "1") (pinfunction "1_1") (pintype "unspecified"))
      (node (ref "C5") (pin "2") (pinfunction "2_2") (pintype "unspecified"))
      (node (ref "C6") (pin "2") (pinfunction "2_2") (pintype "unspecified"))
      (node (ref "C7") (pin "2") (pinfunction "2_2") (pintype "unspecified"))
      (node (ref "C8") (pin "2") (pinfunction "2_2") (pintype "unspecified"))
      (node (ref "C9") (pin "1") (pinfunction "1_1") (pintype "unspecified"))
      (node (ref "D1") (pin "2") (pinfunction "GND_2") (pintype "unspecified"))
      (node (ref "D4") (pin "1") (pinfunction "K_1") (pintype "unspecified"))
      (node (ref "J1") (pin "1") (pinfunction "1_1") (pintype "bidirectional"))
      (node (ref "J1") (pin "13") (pinfunction "13_13") (pintype "bidirectional"))
      (node (ref "J1") (pin "14") (pinfunction "14_14") (pintype "bidirectional"))
      (node (ref "J1") (pin "2") (pinfunction "2_2") (pintype "bidirectional"))
      (node (ref "J1") (pin "22") (pinfunction "22_22") (pintype "bidirectional"))
      (node (ref "J1") (pin "23") (pinfunction "23_23") (pintype "bidirectional"))
      (node (ref "J1") (pin "32") (pinfunction "32_32") (pintype "bidirectional"))
      (node (ref "J1") (pin "33") (pinfunction "33_33") (pintype "bidirectional"))
      (node (ref "J1") (pin "42") (pinfunction "42_42") (pintype "bidirectional"))
      (node (ref "J1") (pin "43") (pinfunction "43_43") (pintype "bidirectional"))
      (node (ref "J1") (pin "52") (pinfunction "52_52") (pintype "bidirectional"))
      (node (ref "J1") (pin "53") (pinfunction "53_53") (pintype "bidirectional"))
      (node (ref "J1") (pin "59") (pinfunction "59_59") (pintype "bidirectional"))
      (node (ref "J1") (pin "60") (pinfunction "60_60") (pintype "bidirectional"))
      (node (ref "J1") (pin "65") (pinfunction "65_65") (pintype "bidirectional"))
      (node (ref "J1") (pin "66") (pinfunction "66_66") (pintype "bidirectional"))
      (node (ref "J1") (pin "7") (pinfunction "7_7") (pintype "bidirectional"))
      (node (ref "J1") (pin "71") (pinfunction "71_71") (pintype "bidirectional"))
      (node (ref "J1") (pin "74") (pinfunction "74_74") (pintype "bidirectional"))
      (node (ref "J1") (pin "8") (pinfunction "8_8") (pintype "bidirectional"))
      (node (ref "J1") (pin "98") (pinfunction "98_98") (pintype "bidirectional"))
      (node (ref "J2") (pin "13") (pinfunction "13_13") (pintype "bidirectional"))
      (node (ref "J2") (pin "14") (pinfunction "14_14") (pintype "bidirectional"))
      (node (ref "J2") (pin "19") (pinfunction "19_19") (pintype "bidirectional"))
      (node (ref "J2") (pin "20") (pinfunction "20_20") (pintype "bidirectional"))
      (node (ref "J2") (pin "7") (pinfunction "7_7") (pintype "bidirectional"))
      (node (ref "J2") (pin "8") (pinfunction "8_8") (pintype "bidirectional"))
      (node (ref "R1") (pin "2") (pinfunction "2_2") (pintype "unspecified"))
      (node (ref "R15") (pin "1") (pinfunction "1_1") (pintype "unspecified"))
      (node (ref "R16") (pin "1") (pinfunction "1_1") (pintype "unspecified"))
      (node (ref "R18") (pin "1") (pinfunction "1_1") (pintype "unspecified"))
      (node (ref "R22") (pin "1") (pinfunction "1_1") (pintype "unspecified"))
      (node (ref "R25") (pin "2") (pinfunction "2_2") (pintype "unspecified"))
      (node (ref "R4") (pin "2") (pinfunction "2_2") (pintype "unspecified"))
      (node (ref "R6") (pin "2") (pinfunction "2_2") (pintype "unspecified"))
      (node (ref "SW1") (pin "1") (pinfunction "1_1") (pintype "unspecified"))
      (node (ref "U1") (pin "21") (pinfunction "21_21") (pintype "unspecified"))
      (node (ref "U1") (pin "22") (pinfunction "22_22") (pintype "unspecified"))
      (node (ref "U1") (pin "23") (pinfunction "23_23") (pintype "unspecified"))
      (node (ref "U1") (pin "24") (pinfunction "24_24") (pintype "unspecified"))
      (node (ref "U1") (pin "25") (pinfunction "25_25") (pintype "unspecified"))
      (node (ref "U1") (pin "26") (pinfunction "26_26") (pintype "unspecified"))
      (node (ref "U1") (pin "27") (pinfunction "27_27") (pintype "unspecified"))
      (node (ref "U1") (pin "28") (pinfunction "28_28") (pintype "unspecified"))
      (node (ref "U10") (pin "1") (pinfunction "1_1") (pintype "unspecified"))
      (node (ref "U11") (pin "1") (pinfunction "1_1") (pintype "unspecified"))
      (node (ref "U12") (pin "2") (pinfunction "GND_2") (pintype "unspecified"))
      (node (ref "U12") (pin "3") (pinfunction "CE#_3") (pintype "unspecified"))
      (node (ref "U13") (pin "2") (pinfunction "GND_2") (pintype "unspecified"))
      (node (ref "U13") (pin "3") (pinfunction "CE#_3") (pintype "unspecified"))
      (node (ref "U2") (pin "21") (pinfunction "21_21") (pintype "unspecified"))
      (node (ref "U2") (pin "22") (pinfunction "22_22") (pintype "unspecified"))
      (node (ref "U2") (pin "23") (pinfunction "23_23") (pintype "unspecified"))
      (node (ref "U2") (pin "24") (pinfunction "24_24") (pintype "unspecified"))
      (node (ref "U2") (pin "25") (pinfunction "25_25") (pintype "unspecified"))
      (node (ref "U2") (pin "26") (pinfunction "26_26") (pintype "unspecified"))
      (node (ref "U2") (pin "27") (pinfunction "27_27") (pintype "unspecified"))
      (node (ref "U2") (pin "28") (pinfunction "28_28") (pintype "unspecified"))
      (node (ref "U3") (pin "1") (pinfunction "GND_1") (pintype "unspecified"))
      (node (ref "U3") (pin "105") (pinfunction "GND_105") (pintype "unspecified"))
      (node (ref "U3") (pin "111") (pinfunction "GND_111") (pintype "unspecified"))
      (node (ref "U3") (pin "115") (pinfunction "PLLGND_115") (pintype "unspecified"))
      (node (ref "U3") (pin "119") (pinfunction "GND_119") (pintype "unspecified"))
      (node (ref "U3") (pin "12") (pinfunction "AGND_12") (pintype "unspecified"))
      (node (ref "U3") (pin "125") (pinfunction "GND_125") (pintype "unspecified"))
      (node (ref "U3") (pin "18") (pinfunction "GND_18") (pintype "unspecified"))
      (node (ref "U3") (pin "24") (pinfunction "GND_24") (pintype "unspecified"))
      (node (ref "U3") (pin "32") (pinfunction "GND_32") (pintype "unspecified"))
      (node (ref "U3") (pin "34") (pinfunction "SGND_34") (pintype "unspecified"))
      (node (ref "U3") (pin "40") (pinfunction "SGND_40") (pintype "unspecified"))
      (node (ref "U3") (pin "43") (pinfunction "GND_43") (pintype "unspecified"))
      (node (ref "U3") (pin "44") (pinfunction "GND_44") (pintype "unspecified"))
      (node (ref "U3") (pin "57") (pinfunction "GND_57") (pintype "unspecified"))
      (node (ref "U3") (pin "61") (pinfunction "GND_SWR_61") (pintype "unspecified"))
      (node (ref "U3") (pin "62") (pinfunction "GND_SWR_62") (pintype "unspecified"))
      (node (ref "U3") (pin "68") (pinfunction "GND_68") (pintype "unspecified"))
      (node (ref "U3") (pin "85") (pinfunction "GND_85") (pintype "unspecified"))
      (node (ref "U3") (pin "89") (pinfunction "GND_89") (pintype "unspecified"))
      (node (ref "U3") (pin "96") (pinfunction "GND_96") (pintype "unspecified"))
      (node (ref "U3") (pin "99") (pinfunction "GND_99") (pintype "unspecified"))
      (node (ref "U4") (pin "7") (pinfunction "GND_7") (pintype "unspecified"))
      (node (ref "U4") (pin "9") (pinfunction "EP_9") (pintype "unspecified"))
      (node (ref "U5") (pin "2") (pinfunction "GND_2") (pintype "unspecified"))
      (node (ref "U6") (pin "5") (pinfunction "RTN_5") (pintype "unspecified"))
      (node (ref "U8") (pin "1") (pinfunction "1_1") (pintype "unspecified"))
      (node (ref "U9") (pin "1") (pinfunction "1_1") (pintype "unspecified"))
      (node (ref "USBC1") (pin "1") (pinfunction "EH_1") (pintype "unspecified"))
      (node (ref "USBC1") (pin "2") (pinfunction "EH_2") (pintype "unspecified"))
      (node (ref "USBC1") (pin "3") (pinfunction "EH_3") (pintype "unspecified"))
      (node (ref "USBC1") (pin "4") (pinfunction "EH_4") (pintype "unspecified"))
      (node (ref "USBC1") (pin "A1B12") (pinfunction "GND_A1B12") (pintype "unspecified"))
      (node (ref "USBC1") (pin "B1A12") (pinfunction "GND_B1A12") (pintype "unspecified"))
      (node (ref "X1") (pin "2") (pinfunction "GND_2") (pintype "unspecified"))
      (node (ref "X1") (pin "4") (pinfunction "GND_4") (pintype "unspecified"))
    )
    (net (code "15") (name "Net-(C1-Pad1)") (class "Default")
      (node (ref "C1") (pin "1") (pinfunction "1_1") (pintype "unspecified"))
      (node (ref "U1") (pin "1") (pinfunction "1_1") (pintype "unspecified"))
      (node (ref "U1") (pin "12") (pinfunction "12_12") (pintype "unspecified"))
      (node (ref "U1") (pin "6") (pinfunction "6_6") (pintype "unspecified"))
      (node (ref "U1") (pin "7") (pinfunction "7_7") (pintype "unspecified"))
    )
    (net (code "16") (name "Net-(C2-Pad1)") (class "Default")
      (node (ref "C2") (pin "1") (pinfunction "1_1") (pintype "unspecified"))
      (node (ref "U2") (pin "1") (pinfunction "1_1") (pintype "unspecified"))
      (node (ref "U2") (pin "12") (pinfunction "12_12") (pintype "unspecified"))
      (node (ref "U2") (pin "6") (pinfunction "6_6") (pintype "unspecified"))
      (node (ref "U2") (pin "7") (pinfunction "7_7") (pintype "unspecified"))
    )
    (net (code "17") (name "Net-(C42-Pad1)") (class "Default")
      (node (ref "C42") (pin "1") (pinfunction "1_1") (pintype "input"))
      (node (ref "R23") (pin "2") (pinfunction "2_2") (pintype "unspecified"))
    )
    (net (code "18") (name "Net-(D4-A)") (class "Default")
      (node (ref "C40") (pin "1") (pinfunction "1_1") (pintype "unspecified"))
      (node (ref "D4") (pin "2") (pinfunction "A_2") (pintype "unspecified"))
      (node (ref "L2") (pin "1") (pinfunction "1_1") (pintype "unspecified"))
      (node (ref "U4") (pin "8") (pinfunction "SW_8") (pintype "unspecified"))
    )
    (net (code "19") (name "Net-(L1-Pad1)") (class "Default")
      (node (ref "L1") (pin "1") (pinfunction "1_1") (pintype "unspecified"))
      (node (ref "U3") (pin "63") (pinfunction "LX_63") (pintype "unspecified"))
      (node (ref "U3") (pin "64") (pinfunction "LX_64") (pintype "unspecified"))
    )
    (net (code "20") (name "Net-(U3-DISAUTOLOAD{slash}GPO45)") (class "Default")
      (node (ref "R2") (pin "1") (pinfunction "1_1") (pintype "unspecified"))
      (node (ref "U3") (pin "76") (pinfunction "DISAUTOLOAD/GPO45_76") (pintype "unspecified"))
    )
    (net (code "21") (name "Net-(U3-DIS_8051{slash}LAN2LED0{slash}GPO44)") (class "Default")
      (node (ref "R3") (pin "1") (pinfunction "1_1") (pintype "unspecified"))
      (node (ref "U3") (pin "75") (pinfunction "DIS_8051/LAN2LED0/GPO44_75") (pintype "unspecified"))
    )
    (net (code "22") (name "Net-(U3-EEPROM_MOD{slash}LAN4LED0{slash}GPO39)") (class "Default")
      (node (ref "R6") (pin "1") (pinfunction "1_1") (pintype "unspecified"))
      (node (ref "U3") (pin "70") (pinfunction "EEPROM_MOD/LAN4LED0/GPO39_70") (pintype "unspecified"))
    )
    (net (code "23") (name "Net-(U3-EN_PWRLIGHT{slash}GPO42)") (class "Default")
      (node (ref "R5") (pin "1") (pinfunction "1_1") (pintype "unspecified"))
      (node (ref "U3") (pin "73") (pinfunction "EN_PWRLIGHT/GPO42_73") (pintype "unspecified"))
    )
    (net (code "24") (name "Net-(U3-EN_SPIF{slash}LAN3LED0{slash}GPO43)") (class "Default")
      (node (ref "R4") (pin "1") (pinfunction "1_1") (pintype "unspecified"))
      (node (ref "U3") (pin "74") (pinfunction "EN_SPIF/LAN3LED0/GPO43_74") (pintype "unspecified"))
    )
    (net (code "25") (name "Net-(U3-MDIREF)") (class "Default")
      (node (ref "R1") (pin "1") (pinfunction "1_1") (pintype "unspecified"))
      (node (ref "U3") (pin "13") (pinfunction "MDIREF_13") (pintype "unspecified"))
    )
    (net (code "26") (name "Net-(U3-SCK{slash}GPIO54)") (class "Default")
      (node (ref "R7") (pin "1") (pinfunction "1_1") (pintype "unspecified"))
      (node (ref "U3") (pin "87") (pinfunction "SCK/GPIO54_87") (pintype "unspecified"))
    )
    (net (code "27") (name "Net-(U3-nRESET)") (class "Default")
      (node (ref "R14") (pin "1") (pinfunction "1_1") (pintype "unspecified"))
      (node (ref "U3") (pin "86") (pinfunction "nRESET_86") (pintype "unspecified"))
    )
    (net (code "28") (name "Net-(U4-BOOT)") (class "Default")
      (node (ref "C40") (pin "2") (pinfunction "2_2") (pintype "unspecified"))
      (node (ref "U4") (pin "1") (pinfunction "BOOT_1") (pintype "unspecified"))
    )
    (net (code "29") (name "Net-(U4-COMP)") (class "Default")
      (node (ref "R23") (pin "1") (pinfunction "1_1") (pintype "unspecified"))
      (node (ref "U4") (pin "6") (pinfunction "COMP_6") (pintype "unspecified"))
    )
    (net (code "30") (name "Net-(U4-FB)") (class "Default")
      (node (ref "R21") (pin "2") (pinfunction "2_2") (pintype "unspecified"))
      (node (ref "R22") (pin "2") (pinfunction "2_2") (pintype "unspecified"))
      (node (ref "U4") (pin "5") (pinfunction "FB_5") (pintype "unspecified"))
    )
    (net (code "31") (name "Net-(U4-RT{slash}CLK)") (class "Default")
      (node (ref "R18") (pin "2") (pinfunction "2_2") (pintype "unspecified"))
      (node (ref "U4") (pin "4") (pinfunction "RT/CLK_4") (pintype "unspecified"))
    )
    (net (code "32") (name "Net-(U5-FB)") (class "Default")
      (node (ref "R24") (pin "1") (pinfunction "1_1") (pintype "unspecified"))
      (node (ref "R25") (pin "1") (pinfunction "1_1") (pintype "unspecified"))
      (node (ref "U5") (pin "5") (pinfunction "FB_5") (pintype "unspecified"))
    )
    (net (code "33") (name "Net-(U5-LX)") (class "Default")
      (node (ref "U5") (pin "3") (pinfunction "LX_3") (pintype "unspecified"))
      (node (ref "U7") (pin "2") (pinfunction "2_2") (pintype "unspecified"))
    )
    (net (code "34") (name "Net-(U6-CLS)") (class "Default")
      (node (ref "R17") (pin "2") (pinfunction "2_2") (pintype "unspecified"))
      (node (ref "U6") (pin "3") (pinfunction "CLS_3") (pintype "unspecified"))
    )
    (net (code "35") (name "Net-(U6-DEN)") (class "Default")
      (node (ref "R20") (pin "2") (pinfunction "2_2") (pintype "unspecified"))
      (node (ref "U6") (pin "2") (pinfunction "DEN_2") (pintype "unspecified"))
    )
    (net (code "36") (name "Net-(USBC1-CC1)") (class "Default")
      (node (ref "C26") (pin "2") (pinfunction "2_2") (pintype "unspecified"))
      (node (ref "R15") (pin "2") (pinfunction "2_2") (pintype "unspecified"))
      (node (ref "USBC1") (pin "A5") (pinfunction "CC1_A5") (pintype "unspecified"))
    )
    (net (code "37") (name "Net-(USBC1-CC2)") (class "Default")
      (node (ref "C27") (pin "2") (pinfunction "2_2") (pintype "unspecified"))
      (node (ref "R16") (pin "2") (pinfunction "2_2") (pintype "unspecified"))
      (node (ref "USBC1") (pin "B5") (pinfunction "CC2_B5") (pintype "unspecified"))
    )
    (net (code "38") (name "P0_TXA_N") (class "Default")
      (node (ref "U1") (pin "9") (pinfunction "9_9") (pintype "unspecified"))
      (node (ref "U3") (pin "92") (pinfunction "P0MDIAN_92") (pintype "unspecified"))
    )
    (net (code "39") (name "P0_TXA_P") (class "Default")
      (node (ref "U1") (pin "8") (pinfunction "8_8") (pintype "unspecified"))
      (node (ref "U3") (pin "91") (pinfunction "P0MDIAP_91") (pintype "unspecified"))
    )
    (net (code "40") (name "P0_TXB_N") (class "Default")
      (node (ref "U1") (pin "2") (pinfunction "2_2") (pintype "unspecified"))
      (node (ref "U3") (pin "94") (pinfunction "P0MDIBN_94") (pintype "unspecified"))
    )
    (net (code "41") (name "P0_TXB_P") (class "Default")
      (node (ref "U1") (pin "3") (pinfunction "3_3") (pintype "unspecified"))
      (node (ref "U3") (pin "93") (pinfunction "P0MDIBP_93") (pintype "unspecified"))
    )
    (net (code "42") (name "P0_TXC_N") (class "Default")
      (node (ref "U1") (pin "5") (pinfunction "5_5") (pintype "unspecified"))
      (node (ref "U3") (pin "98") (pinfunction "P0MDICN_98") (pintype "unspecified"))
    )
    (net (code "43") (name "P0_TXC_P") (class "Default")
      (node (ref "U1") (pin "4") (pinfunction "4_4") (pintype "unspecified"))
      (node (ref "U3") (pin "97") (pinfunction "P0MDICP_97") (pintype "unspecified"))
    )
    (net (code "44") (name "P0_TXD_N") (class "Default")
      (node (ref "U1") (pin "10") (pinfunction "10_10") (pintype "unspecified"))
      (node (ref "U3") (pin "101") (pinfunction "P0MDIDN_101") (pintype "unspecified"))
    )
    (net (code "45") (name "P0_TXD_P") (class "Default")
      (node (ref "U1") (pin "11") (pinfunction "11_11") (pintype "unspecified"))
      (node (ref "U3") (pin "100") (pinfunction "P0MDIDP_100") (pintype "unspecified"))
    )
    (net (code "46") (name "P1_TXA_N") (class "Default")
      (node (ref "U2") (pin "9") (pinfunction "9_9") (pintype "unspecified"))
      (node (ref "U3") (pin "104") (pinfunction "P1MDIAN_104") (pintype "unspecified"))
    )
    (net (code "47") (name "P1_TXA_P") (class "Default")
      (node (ref "U2") (pin "8") (pinfunction "8_8") (pintype "unspecified"))
      (node (ref "U3") (pin "103") (pinfunction "P1MDIAP_103") (pintype "unspecified"))
    )
    (net (code "48") (name "P1_TXB_N") (class "Default")
      (node (ref "U2") (pin "2") (pinfunction "2_2") (pintype "unspecified"))
      (node (ref "U3") (pin "107") (pinfunction "P1MDIBN_107") (pintype "unspecified"))
    )
    (net (code "49") (name "P1_TXB_P") (class "Default")
      (node (ref "U2") (pin "3") (pinfunction "3_3") (pintype "unspecified"))
      (node (ref "U3") (pin "106") (pinfunction "P1MDIBP_106") (pintype "unspecified"))
    )
    (net (code "50") (name "P1_TXC_N") (class "Default")
      (node (ref "U2") (pin "5") (pinfunction "5_5") (pintype "unspecified"))
      (node (ref "U3") (pin "110") (pinfunction "P1MDICN_110") (pintype "unspecified"))
    )
    (net (code "51") (name "P1_TXC_P") (class "Default")
      (node (ref "U2") (pin "4") (pinfunction "4_4") (pintype "unspecified"))
      (node (ref "U3") (pin "109") (pinfunction "P1MDICP_109") (pintype "unspecified"))
    )
    (net (code "52") (name "P1_TXD_N") (class "Default")
      (node (ref "U2") (pin "10") (pinfunction "10_10") (pintype "unspecified"))
      (node (ref "U3") (pin "113") (pinfunction "P1MDIDN_113") (pintype "unspecified"))
    )
    (net (code "53") (name "P1_TXD_P") (class "Default")
      (node (ref "U2") (pin "11") (pinfunction "11_11") (pintype "unspecified"))
      (node (ref "U3") (pin "112") (pinfunction "P1MDIDP_112") (pintype "unspecified"))
    )
    (net (code "54") (name "POE_48V") (class "Default")
      (node (ref "C39") (pin "1") (pinfunction "1_1") (pintype "unspecified"))
      (node (ref "C41") (pin "1") (pinfunction "1_1") (pintype "unspecified"))
      (node (ref "D2") (pin "3") (pinfunction "+_3") (pintype "unspecified"))
      (node (ref "D3") (pin "3") (pinfunction "+_3") (pintype "unspecified"))
      (node (ref "R19") (pin "2") (pinfunction "2_2") (pintype "unspecified"))
      (node (ref "R20") (pin "1") (pinfunction "1_1") (pintype "unspecified"))
      (node (ref "U4") (pin "2") (pinfunction "VIN_2") (pintype "unspecified"))
      (node (ref "U6") (pin "1") (pinfunction "VDD_1") (pintype "unspecified"))
    )
    (net (code "55") (name "POE_PWR") (class "Default")
      (node (ref "C43") (pin "1") (pinfunction "1_1") (pintype "unspecified"))
      (node (ref "C44") (pin "1") (pinfunction "1_1") (pintype "unspecified"))
      (node (ref "L2") (pin "2") (pinfunction "2_2") (pintype "unspecified"))
      (node (ref "R21") (pin "1") (pinfunction "1_1") (pintype "unspecified"))
      (node (ref "U13") (pin "1") (pinfunction "VIN_1") (pintype "unspecified"))
    )
    (net (code "56") (name "POE_VC12") (class "Default")
      (node (ref "D2") (pin "1") (pinfunction "AC_1") (pintype "unspecified"))
      (node (ref "U1") (pin "13") (pinfunction "13_13") (pintype "unspecified"))
    )
    (net (code "57") (name "POE_VC36") (class "Default")
      (node (ref "D2") (pin "2") (pinfunction "AC_2") (pintype "unspecified"))
      (node (ref "U1") (pin "14") (pinfunction "14_14") (pintype "unspecified"))
    )
    (net (code "58") (name "POE_VC45") (class "Default")
      (node (ref "D3") (pin "1") (pinfunction "AC_1") (pintype "unspecified"))
      (node (ref "U1") (pin "15") (pinfunction "15_15") (pintype "unspecified"))
    )
    (net (code "59") (name "POE_VC78") (class "Default")
      (node (ref "D3") (pin "2") (pinfunction "AC_2") (pintype "unspecified"))
      (node (ref "U1") (pin "16") (pinfunction "16_16") (pintype "unspecified"))
    )
    (net (code "60") (name "TPS5EN") (class "Default")
      (node (ref "R19") (pin "1") (pinfunction "1_1") (pintype "unspecified"))
      (node (ref "U4") (pin "3") (pinfunction "EN_3") (pintype "unspecified"))
    )
    (net (code "61") (name "U1_LED_GRN_N") (class "Default")
      (node (ref "R13") (pin "1") (pinfunction "1_1") (pintype "unspecified"))
      (node (ref "U1") (pin "17") (pinfunction "17_17") (pintype "unspecified"))
      (node (ref "U3") (pin "81") (pinfunction "SMI_SEL/LED_CK/LAN0LED0/GPO52_81") (pintype "unspecified"))
    )
    (net (code "62") (name "U1_LED_GRN_P") (class "Default")
      (node (ref "R8") (pin "2") (pinfunction "2_2") (pintype "unspecified"))
      (node (ref "U1") (pin "18") (pinfunction "18_18") (pintype "unspecified"))
    )
    (net (code "63") (name "U1_LED_YEL_N") (class "Default")
      (node (ref "U1") (pin "19") (pinfunction "19_19") (pintype "unspecified"))
      (node (ref "U3") (pin "80") (pinfunction "LED_DA/LAN0LED1/GPO51_80") (pintype "unspecified"))
    )
    (net (code "64") (name "U1_LED_YEL_P") (class "Default")
      (node (ref "R9") (pin "2") (pinfunction "2_2") (pintype "unspecified"))
      (node (ref "U1") (pin "20") (pinfunction "20_20") (pintype "unspecified"))
    )
    (net (code "65") (name "U2_LED_GRN_N") (class "Default")
      (node (ref "R12") (pin "1") (pinfunction "1_1") (pintype "unspecified"))
      (node (ref "U2") (pin "17") (pinfunction "17_17") (pintype "unspecified"))
      (node (ref "U3") (pin "79") (pinfunction "EN_PHY/LAN1LED0/GPO50_79") (pintype "unspecified"))
    )
    (net (code "66") (name "U2_LED_GRN_P") (class "Default")
      (node (ref "R10") (pin "2") (pinfunction "2_2") (pintype "unspecified"))
      (node (ref "U2") (pin "18") (pinfunction "18_18") (pintype "unspecified"))
    )
    (net (code "67") (name "U2_LED_YEL_N") (class "Default")
      (node (ref "U2") (pin "19") (pinfunction "19_19") (pintype "unspecified"))
      (node (ref "U3") (pin "78") (pinfunction "LAN1LED1/GPIO49_78") (pintype "unspecified"))
    )
    (net (code "68") (name "U2_LED_YEL_P") (class "Default")
      (node (ref "R11") (pin "2") (pinfunction "2_2") (pintype "unspecified"))
      (node (ref "U2") (pin "20") (pinfunction "20_20") (pintype "unspecified"))
    )
    (net (code "69") (name "USB_N") (class "Default")
      (node (ref "D1") (pin "3") (pinfunction "IO2_3") (pintype "unspecified"))
      (node (ref "J2") (pin "3") (pinfunction "3_3") (pintype "bidirectional"))
    )
    (net (code "70") (name "USB_P") (class "Default")
      (node (ref "D1") (pin "1") (pinfunction "IO1_1") (pintype "unspecified"))
      (node (ref "J2") (pin "5") (pinfunction "5_5") (pintype "bidirectional"))
    )
    (net (code "71") (name "USB_PWR") (class "Default")
      (node (ref "C24") (pin "1") (pinfunction "1_1") (pintype "unspecified"))
      (node (ref "C25") (pin "1") (pinfunction "1_1") (pintype "input"))
      (node (ref "D1") (pin "5") (pinfunction "VBUS_5") (pintype "unspecified"))
      (node (ref "U12") (pin "1") (pinfunction "VIN_1") (pintype "unspecified"))
      (node (ref "USBC1") (pin "A4B9") (pinfunction "VBUS_A4B9") (pintype "unspecified"))
      (node (ref "USBC1") (pin "B4A9") (pinfunction "VBUS_B4A9") (pintype "unspecified"))
    )
    (net (code "72") (name "USB_UP_N") (class "Default")
      (node (ref "D1") (pin "4") (pinfunction "IO2_4") (pintype "unspecified"))
      (node (ref "USBC1") (pin "A7") (pinfunction "DN1_A7") (pintype "unspecified"))
      (node (ref "USBC1") (pin "B7") (pinfunction "DN2_B7") (pintype "unspecified"))
    )
    (net (code "73") (name "USB_UP_P") (class "Default")
      (node (ref "D1") (pin "6") (pinfunction "IO1_6") (pintype "unspecified"))
      (node (ref "USBC1") (pin "A6") (pinfunction "DP1_A6") (pintype "unspecified"))
      (node (ref "USBC1") (pin "B6") (pinfunction "DP2_B6") (pintype "unspecified"))
    )
    (net (code "74") (name "VCC") (class "Default")
      (node (ref "C10") (pin "2") (pinfunction "2_2") (pintype "unspecified"))
      (node (ref "C11") (pin "2") (pinfunction "2_2") (pintype "unspecified"))
      (node (ref "C12") (pin "2") (pinfunction "2_2") (pintype "unspecified"))
      (node (ref "C13") (pin "2") (pinfunction "2_2") (pintype "unspecified"))
      (node (ref "C14") (pin "2") (pinfunction "2_2") (pintype "unspecified"))
      (node (ref "C15") (pin "2") (pinfunction "2_2") (pintype "unspecified"))
      (node (ref "C16") (pin "2") (pinfunction "2_2") (pintype "unspecified"))
      (node (ref "C17") (pin "2") (pinfunction "2_2") (pintype "unspecified"))
      (node (ref "C18") (pin "2") (pinfunction "2_2") (pintype "unspecified"))
      (node (ref "C19") (pin "2") (pinfunction "2_2") (pintype "unspecified"))
      (node (ref "C20") (pin "2") (pinfunction "2_2") (pintype "unspecified"))
      (node (ref "C21") (pin "2") (pinfunction "2_2") (pintype "unspecified"))
      (node (ref "C22") (pin "2") (pinfunction "2_2") (pintype "unspecified"))
      (node (ref "C23") (pin "2") (pinfunction "2_2") (pintype "unspecified"))
      (node (ref "C4") (pin "2") (pinfunction "2_2") (pintype "unspecified"))
      (node (ref "C45") (pin "2") (pinfunction "2_2") (pintype "unspecified"))
      (node (ref "C5") (pin "1") (pinfunction "1_1") (pintype "unspecified"))
      (node (ref "C6") (pin "1") (pinfunction "1_1") (pintype "unspecified"))
      (node (ref "C9") (pin "2") (pinfunction "2_2") (pintype "unspecified"))
      (node (ref "R10") (pin "1") (pinfunction "1_1") (pintype "unspecified"))
      (node (ref "R11") (pin "1") (pinfunction "1_1") (pintype "unspecified"))
      (node (ref "R12") (pin "2") (pinfunction "2_2") (pintype "unspecified"))
      (node (ref "R13") (pin "2") (pinfunction "2_2") (pintype "unspecified"))
      (node (ref "R14") (pin "2") (pinfunction "2_2") (pintype "unspecified"))
      (node (ref "R2") (pin "2") (pinfunction "2_2") (pintype "unspecified"))
      (node (ref "R24") (pin "2") (pinfunction "2_2") (pintype "unspecified"))
      (node (ref "R3") (pin "2") (pinfunction "2_2") (pintype "unspecified"))
      (node (ref "R5") (pin "2") (pinfunction "2_2") (pintype "unspecified"))
      (node (ref "R7") (pin "2") (pinfunction "2_2") (pintype "unspecified"))
      (node (ref "R8") (pin "1") (pinfunction "1_1") (pintype "unspecified"))
      (node (ref "R9") (pin "1") (pinfunction "1_1") (pintype "unspecified"))
      (node (ref "U3") (pin "102") (pinfunction "AVDDH_102") (pintype "unspecified"))
      (node (ref "U3") (pin "11") (pinfunction "AVDDH_11") (pintype "unspecified"))
      (node (ref "U3") (pin "116") (pinfunction "AVDDH_116") (pintype "unspecified"))
      (node (ref "U3") (pin "128") (pinfunction "AVDDH_128") (pintype "unspecified"))
      (node (ref "U3") (pin "17") (pinfunction "AVDDH_17") (pintype "unspecified"))
      (node (ref "U3") (pin "21") (pinfunction "AVDDH_21") (pintype "unspecified"))
      (node (ref "U3") (pin "33") (pinfunction "AVDDH_33") (pintype "unspecified"))
      (node (ref "U3") (pin "41") (pinfunction "SVDDH_41") (pintype "unspecified"))
      (node (ref "U3") (pin "42") (pinfunction "DVDDIO_2_42") (pintype "unspecified"))
      (node (ref "U3") (pin "59") (pinfunction "DVDDIO_2_59") (pintype "unspecified"))
      (node (ref "U3") (pin "60") (pinfunction "EN_SWR_60") (pintype "unspecified"))
      (node (ref "U3") (pin "65") (pinfunction "HV_SWR_65") (pintype "unspecified"))
      (node (ref "U3") (pin "66") (pinfunction "HV_SWR_66") (pintype "unspecified"))
      (node (ref "U3") (pin "67") (pinfunction "DVDDIO_67") (pintype "unspecified"))
      (node (ref "U3") (pin "82") (pinfunction "AVDDH_82") (pintype "unspecified"))
      (node (ref "U3") (pin "90") (pinfunction "AVDDH_90") (pintype "unspecified"))
      (node (ref "U7") (pin "1") (pinfunction "1_1") (pintype "unspecified"))
    )
    (net (code "75") (name "VSS_POE") (class "Default")
      (node (ref "C39") (pin "2") (pinfunction "2_2") (pintype "unspecified"))
      (node (ref "D2") (pin "4") (pinfunction "-_4") (pintype "unspecified"))
      (node (ref "D3") (pin "4") (pinfunction "-_4") (pintype "unspecified"))
      (node (ref "R17") (pin "1") (pinfunction "1_1") (pintype "unspecified"))
      (node (ref "U6") (pin "4") (pinfunction "VSS_4") (pintype "unspecified"))
      (node (ref "U6") (pin "8") (pinfunction "APD_8") (pintype "unspecified"))
      (node (ref "U6") (pin "9") (pinfunction "EP_9") (pintype "unspecified"))
    )
    (net (code "76") (name "nRPIBOOT") (class "Default")
      (node (ref "J1") (pin "93") (pinfunction "93_93") (pintype "bidirectional"))
      (node (ref "SW1") (pin "2") (pinfunction "2_2") (pintype "unspecified"))
    )
    (net (code "77") (name "unconnected-(J1-Pad15)") (class "Default")
      (node (ref "J1") (pin "15") (pinfunction "15_15") (pintype "bidirectional+no_connect"))
    )
    (net (code "78") (name "unconnected-(J1-Pad16)") (class "Default")
      (node (ref "J1") (pin "16") (pinfunction "16_16") (pintype "bidirectional+no_connect"))
    )
    (net (code "79") (name "unconnected-(J1-Pad17)") (class "Default")
      (node (ref "J1") (pin "17") (pinfunction "17_17") (pintype "bidirectional+no_connect"))
    )
    (net (code "80") (name "unconnected-(J1-Pad18)") (class "Default")
      (node (ref "J1") (pin "18") (pinfunction "18_18") (pintype "bidirectional+no_connect"))
    )
    (net (code "81") (name "unconnected-(J1-Pad19)") (class "Default")
      (node (ref "J1") (pin "19") (pinfunction "19_19") (pintype "bidirectional+no_connect"))
    )
    (net (code "82") (name "unconnected-(J1-Pad20)") (class "Default")
      (node (ref "J1") (pin "20") (pinfunction "20_20") (pintype "bidirectional+no_connect"))
    )
    (net (code "83") (name "unconnected-(J1-Pad21)") (class "Default")
      (node (ref "J1") (pin "21") (pinfunction "21_21") (pintype "bidirectional+no_connect"))
    )
    (net (code "84") (name "unconnected-(J1-Pad24)") (class "Default")
      (node (ref "J1") (pin "24") (pinfunction "24_24") (pintype "bidirectional+no_connect"))
    )
    (net (code "85") (name "unconnected-(J1-Pad25)") (class "Default")
      (node (ref "J1") (pin "25") (pinfunction "25_25") (pintype "bidirectional+no_connect"))
    )
    (net (code "86") (name "unconnected-(J1-Pad26)") (class "Default")
      (node (ref "J1") (pin "26") (pinfunction "26_26") (pintype "bidirectional+no_connect"))
    )
    (net (code "87") (name "unconnected-(J1-Pad27)") (class "Default")
      (node (ref "J1") (pin "27") (pinfunction "27_27") (pintype "bidirectional+no_connect"))
    )
    (net (code "88") (name "unconnected-(J1-Pad28)") (class "Default")
      (node (ref "J1") (pin "28") (pinfunction "28_28") (pintype "bidirectional+no_connect"))
    )
    (net (code "89") (name "unconnected-(J1-Pad29)") (class "Default")
      (node (ref "J1") (pin "29") (pinfunction "29_29") (pintype "bidirectional+no_connect"))
    )
    (net (code "90") (name "unconnected-(J1-Pad30)") (class "Default")
      (node (ref "J1") (pin "30") (pinfunction "30_30") (pintype "bidirectional+no_connect"))
    )
    (net (code "91") (name "unconnected-(J1-Pad31)") (class "Default")
      (node (ref "J1") (pin "31") (pinfunction "31_31") (pintype "bidirectional+no_connect"))
    )
    (net (code "92") (name "unconnected-(J1-Pad34)") (class "Default")
      (node (ref "J1") (pin "34") (pinfunction "34_34") (pintype "bidirectional+no_connect"))
    )
    (net (code "93") (name "unconnected-(J1-Pad35)") (class "Default")
      (node (ref "J1") (pin "35") (pinfunction "35_35") (pintype "bidirectional+no_connect"))
    )
    (net (code "94") (name "unconnected-(J1-Pad36)") (class "Default")
      (node (ref "J1") (pin "36") (pinfunction "36_36") (pintype "bidirectional+no_connect"))
    )
    (net (code "95") (name "unconnected-(J1-Pad37)") (class "Default")
      (node (ref "J1") (pin "37") (pinfunction "37_37") (pintype "bidirectional+no_connect"))
    )
    (net (code "96") (name "unconnected-(J1-Pad38)") (class "Default")
      (node (ref "J1") (pin "38") (pinfunction "38_38") (pintype "bidirectional+no_connect"))
    )
    (net (code "97") (name "unconnected-(J1-Pad39)") (class "Default")
      (node (ref "J1") (pin "39") (pinfunction "39_39") (pintype "bidirectional+no_connect"))
    )
    (net (code "98") (name "unconnected-(J1-Pad40)") (class "Default")
      (node (ref "J1") (pin "40") (pinfunction "40_40") (pintype "bidirectional+no_connect"))
    )
    (net (code "99") (name "unconnected-(J1-Pad41)") (class "Default")
      (node (ref "J1") (pin "41") (pinfunction "41_41") (pintype "bidirectional+no_connect"))
    )
    (net (code "100") (name "unconnected-(J1-Pad44)") (class "Default")
      (node (ref "J1") (pin "44") (pinfunction "44_44") (pintype "bidirectional+no_connect"))
    )
    (net (code "101") (name "unconnected-(J1-Pad45)") (class "Default")
      (node (ref "J1") (pin "45") (pinfunction "45_45") (pintype "bidirectional+no_connect"))
    )
    (net (code "102") (name "unconnected-(J1-Pad46)") (class "Default")
      (node (ref "J1") (pin "46") (pinfunction "46_46") (pintype "bidirectional+no_connect"))
    )
    (net (code "103") (name "unconnected-(J1-Pad47)") (class "Default")
      (node (ref "J1") (pin "47") (pinfunction "47_47") (pintype "bidirectional+no_connect"))
    )
    (net (code "104") (name "unconnected-(J1-Pad48)") (class "Default")
      (node (ref "J1") (pin "48") (pinfunction "48_48") (pintype "bidirectional+no_connect"))
    )
    (net (code "105") (name "unconnected-(J1-Pad49)") (class "Default")
      (node (ref "J1") (pin "49") (pinfunction "49_49") (pintype "bidirectional+no_connect"))
    )
    (net (code "106") (name "unconnected-(J1-Pad50)") (class "Default")
      (node (ref "J1") (pin "50") (pinfunction "50_50") (pintype "bidirectional+no_connect"))
    )
    (net (code "107") (name "unconnected-(J1-Pad51)") (class "Default")
      (node (ref "J1") (pin "51") (pinfunction "51_51") (pintype "bidirectional+no_connect"))
    )
    (net (code "108") (name "unconnected-(J1-Pad54)") (class "Default")
      (node (ref "J1") (pin "54") (pinfunction "54_54") (pintype "bidirectional+no_connect"))
    )
    (net (code "109") (name "unconnected-(J1-Pad55)") (class "Default")
      (node (ref "J1") (pin "55") (pinfunction "55_55") (pintype "bidirectional+no_connect"))
    )
    (net (code "110") (name "unconnected-(J1-Pad56)") (class "Default")
      (node (ref "J1") (pin "56") (pinfunction "56_56") (pintype "bidirectional+no_connect"))
    )
    (net (code "111") (name "unconnected-(J1-Pad57)") (class "Default")
      (node (ref "J1") (pin "57") (pinfunction "57_57") (pintype "bidirectional+no_connect"))
    )
    (net (code "112") (name "unconnected-(J1-Pad58)") (class "Default")
      (node (ref "J1") (pin "58") (pinfunction "58_58") (pintype "bidirectional+no_connect"))
    )
    (net (code "113") (name "unconnected-(J1-Pad61)") (class "Default")
      (node (ref "J1") (pin "61") (pinfunction "61_61") (pintype "bidirectional+no_connect"))
    )
    (net (code "114") (name "unconnected-(J1-Pad62)") (class "Default")
      (node (ref "J1") (pin "62") (pinfunction "62_62") (pintype "bidirectional+no_connect"))
    )
    (net (code "115") (name "unconnected-(J1-Pad63)") (class "Default")
      (node (ref "J1") (pin "63") (pinfunction "63_63") (pintype "bidirectional+no_connect"))
    )
    (net (code "116") (name "unconnected-(J1-Pad64)") (class "Default")
      (node (ref "J1") (pin "64") (pinfunction "64_64") (pintype "bidirectional+no_connect"))
    )
    (net (code "117") (name "unconnected-(J1-Pad67)") (class "Default")
      (node (ref "J1") (pin "67") (pinfunction "67_67") (pintype "bidirectional+no_connect"))
    )
    (net (code "118") (name "unconnected-(J1-Pad68)") (class "Default")
      (node (ref "J1") (pin "68") (pinfunction "68_68") (pintype "bidirectional+no_connect"))
    )
    (net (code "119") (name "unconnected-(J1-Pad69)") (class "Default")
      (node (ref "J1") (pin "69") (pinfunction "69_69") (pintype "bidirectional+no_connect"))
    )
    (net (code "120") (name "unconnected-(J1-Pad70)") (class "Default")
      (node (ref "J1") (pin "70") (pinfunction "70_70") (pintype "bidirectional+no_connect"))
    )
    (net (code "121") (name "unconnected-(J1-Pad72)") (class "Default")
      (node (ref "J1") (pin "72") (pinfunction "72_72") (pintype "bidirectional+no_connect"))
    )
    (net (code "122") (name "unconnected-(J1-Pad73)") (class "Default")
      (node (ref "J1") (pin "73") (pinfunction "73_73") (pintype "bidirectional+no_connect"))
    )
    (net (code "123") (name "unconnected-(J1-Pad75)") (class "Default")
      (node (ref "J1") (pin "75") (pinfunction "75_75") (pintype "bidirectional+no_connect"))
    )
    (net (code "124") (name "unconnected-(J1-Pad76)") (class "Default")
      (node (ref "J1") (pin "76") (pinfunction "76_76") (pintype "bidirectional+no_connect"))
    )
    (net (code "125") (name "unconnected-(J1-Pad80)") (class "Default")
      (node (ref "J1") (pin "80") (pinfunction "80_80") (pintype "bidirectional+no_connect"))
    )
    (net (code "126") (name "unconnected-(J1-Pad82)") (class "Default")
      (node (ref "J1") (pin "82") (pinfunction "82_82") (pintype "bidirectional+no_connect"))
    )
    (net (code "127") (name "unconnected-(J1-Pad88)") (class "Default")
      (node (ref "J1") (pin "88") (pinfunction "88_88") (pintype "bidirectional+no_connect"))
    )
    (net (code "128") (name "unconnected-(J1-Pad89)") (class "Default")
      (node (ref "J1") (pin "89") (pinfunction "89_89") (pintype "bidirectional+no_connect"))
    )
    (net (code "129") (name "unconnected-(J1-Pad90)") (class "Default")
      (node (ref "J1") (pin "90") (pinfunction "90_90") (pintype "bidirectional+no_connect"))
    )
    (net (code "130") (name "unconnected-(J1-Pad91)") (class "Default")
      (node (ref "J1") (pin "91") (pinfunction "91_91") (pintype "bidirectional+no_connect"))
    )
    (net (code "131") (name "unconnected-(J1-Pad92)") (class "Default")
      (node (ref "J1") (pin "92") (pinfunction "92_92") (pintype "bidirectional+no_connect"))
    )
    (net (code "132") (name "unconnected-(J1-Pad94)") (class "Default")
      (node (ref "J1") (pin "94") (pinfunction "94_94") (pintype "bidirectional+no_connect"))
    )
    (net (code "133") (name "unconnected-(J1-Pad95)") (class "Default")
      (node (ref "J1") (pin "95") (pinfunction "95_95") (pintype "bidirectional+no_connect"))
    )
    (net (code "134") (name "unconnected-(J1-Pad96)") (class "Default")
      (node (ref "J1") (pin "96") (pinfunction "96_96") (pintype "bidirectional+no_connect"))
    )
    (net (code "135") (name "unconnected-(J1-Pad97)") (class "Default")
      (node (ref "J1") (pin "97") (pinfunction "97_97") (pintype "bidirectional+no_connect"))
    )
    (net (code "136") (name "unconnected-(J1-Pad99)") (class "Default")
      (node (ref "J1") (pin "99") (pinfunction "99_99") (pintype "bidirectional+no_connect"))
    )
    (net (code "137") (name "unconnected-(J1-Pad100)") (class "Default")
      (node (ref "J1") (pin "100") (pinfunction "100_100") (pintype "bidirectional+no_connect"))
    )
    (net (code "138") (name "unconnected-(J2-Pad1)") (class "Default")
      (node (ref "J2") (pin "1") (pinfunction "1_1") (pintype "bidirectional+no_connect"))
    )
    (net (code "139") (name "unconnected-(J2-Pad2)") (class "Default")
      (node (ref "J2") (pin "2") (pinfunction "2_2") (pintype "bidirectional+no_connect"))
    )
    (net (code "140") (name "unconnected-(J2-Pad4)") (class "Default")
      (node (ref "J2") (pin "4") (pinfunction "4_4") (pintype "bidirectional+no_connect"))
    )
    (net (code "141") (name "unconnected-(J2-Pad6)") (class "Default")
      (node (ref "J2") (pin "6") (pinfunction "6_6") (pintype "bidirectional+no_connect"))
    )
    (net (code "142") (name "unconnected-(J2-Pad9)") (class "Default")
      (node (ref "J2") (pin "9") (pinfunction "9_9") (pintype "bidirectional+no_connect"))
    )
    (net (code "143") (name "unconnected-(J2-Pad10)") (class "Default")
      (node (ref "J2") (pin "10") (pinfunction "10_10") (pintype "bidirectional+no_connect"))
    )
    (net (code "144") (name "unconnected-(J2-Pad11)") (class "Default")
      (node (ref "J2") (pin "11") (pinfunction "11_11") (pintype "bidirectional+no_connect"))
    )
    (net (code "145") (name "unconnected-(J2-Pad12)") (class "Default")
      (node (ref "J2") (pin "12") (pinfunction "12_12") (pintype "bidirectional+no_connect"))
    )
    (net (code "146") (name "unconnected-(J2-Pad15)") (class "Default")
      (node (ref "J2") (pin "15") (pinfunction "15_15") (pintype "bidirectional+no_connect"))
    )
    (net (code "147") (name "unconnected-(J2-Pad16)") (class "Default")
      (node (ref "J2") (pin "16") (pinfunction "16_16") (pintype "bidirectional+no_connect"))
    )
    (net (code "148") (name "unconnected-(J2-Pad17)") (class "Default")
      (node (ref "J2") (pin "17") (pinfunction "17_17") (pintype "bidirectional+no_connect"))
    )
    (net (code "149") (name "unconnected-(J2-Pad18)") (class "Default")
      (node (ref "J2") (pin "18") (pinfunction "18_18") (pintype "bidirectional+no_connect"))
    )
    (net (code "150") (name "unconnected-(J2-Pad21)") (class "Default")
      (node (ref "J2") (pin "21") (pinfunction "21_21") (pintype "bidirectional+no_connect"))
    )
    (net (code "151") (name "unconnected-(J2-Pad22)") (class "Default")
      (node (ref "J2") (pin "22") (pinfunction "22_22") (pintype "bidirectional+no_connect"))
    )
    (net (code "152") (name "unconnected-(J2-Pad23)") (class "Default")
      (node (ref "J2") (pin "23") (pinfunction "23_23") (pintype "bidirectional+no_connect"))
    )
    (net (code "153") (name "unconnected-(J2-Pad24)") (class "Default")
      (node (ref "J2") (pin "24") (pinfunction "24_24") (pintype "bidirectional+no_connect"))
    )
    (net (code "154") (name "unconnected-(J2-Pad25)") (class "Default")
      (node (ref "J2") (pin "25") (pinfunction "25_25") (pintype "bidirectional+no_connect"))
    )
    (net (code "155") (name "unconnected-(J2-Pad26)") (class "Default")
      (node (ref "J2") (pin "26") (pinfunction "26_26") (pintype "bidirectional+no_connect"))
    )
    (net (code "156") (name "unconnected-(J2-Pad27)") (class "Default")
      (node (ref "J2") (pin "27") (pinfunction "27_27") (pintype "bidirectional+no_connect"))
    )
    (net (code "157") (name "unconnected-(J2-Pad28)") (class "Default")
      (node (ref "J2") (pin "28") (pinfunction "28_28") (pintype "bidirectional+no_connect"))
    )
    (net (code "158") (name "unconnected-(J2-Pad29)") (class "Default")
      (node (ref "J2") (pin "29") (pinfunction "29_29") (pintype "bidirectional+no_connect"))
    )
    (net (code "159") (name "unconnected-(J2-Pad30)") (class "Default")
      (node (ref "J2") (pin "30") (pinfunction "30_30") (pintype "bidirectional+no_connect"))
    )
    (net (code "160") (name "unconnected-(J2-Pad31)") (class "Default")
      (node (ref "J2") (pin "31") (pinfunction "31_31") (pintype "bidirectional+no_connect"))
    )
    (net (code "161") (name "unconnected-(J2-Pad32)") (class "Default")
      (node (ref "J2") (pin "32") (pinfunction "32_32") (pintype "bidirectional+no_connect"))
    )
    (net (code "162") (name "unconnected-(J2-Pad33)") (class "Default")
      (node (ref "J2") (pin "33") (pinfunction "33_33") (pintype "bidirectional+no_connect"))
    )
    (net (code "163") (name "unconnected-(J2-Pad34)") (class "Default")
      (node (ref "J2") (pin "34") (pinfunction "34_34") (pintype "bidirectional+no_connect"))
    )
    (net (code "164") (name "unconnected-(J2-Pad35)") (class "Default")
      (node (ref "J2") (pin "35") (pinfunction "35_35") (pintype "bidirectional+no_connect"))
    )
    (net (code "165") (name "unconnected-(J2-Pad36)") (class "Default")
      (node (ref "J2") (pin "36") (pinfunction "36_36") (pintype "bidirectional+no_connect"))
    )
    (net (code "166") (name "unconnected-(J2-Pad37)") (class "Default")
      (node (ref "J2") (pin "37") (pinfunction "37_37") (pintype "bidirectional+no_connect"))
    )
    (net (code "167") (name "unconnected-(J2-Pad38)") (class "Default")
      (node (ref "J2") (pin "38") (pinfunction "38_38") (pintype "bidirectional+no_connect"))
    )
    (net (code "168") (name "unconnected-(J2-Pad39)") (class "Default")
      (node (ref "J2") (pin "39") (pinfunction "39_39") (pintype "bidirectional+no_connect"))
    )
    (net (code "169") (name "unconnected-(J2-Pad40)") (class "Default")
      (node (ref "J2") (pin "40") (pinfunction "40_40") (pintype "bidirectional+no_connect"))
    )
    (net (code "170") (name "unconnected-(J2-Pad41)") (class "Default")
      (node (ref "J2") (pin "41") (pinfunction "41_41") (pintype "bidirectional+no_connect"))
    )
    (net (code "171") (name "unconnected-(J2-Pad42)") (class "Default")
      (node (ref "J2") (pin "42") (pinfunction "42_42") (pintype "bidirectional+no_connect"))
    )
    (net (code "172") (name "unconnected-(J2-Pad43)") (class "Default")
      (node (ref "J2") (pin "43") (pinfunction "43_43") (pintype "bidirectional+no_connect"))
    )
    (net (code "173") (name "unconnected-(J2-Pad44)") (class "Default")
      (node (ref "J2") (pin "44") (pinfunction "44_44") (pintype "bidirectional+no_connect"))
    )
    (net (code "174") (name "unconnected-(J2-Pad45)") (class "Default")
      (node (ref "J2") (pin "45") (pinfunction "45_45") (pintype "bidirectional+no_connect"))
    )
    (net (code "175") (name "unconnected-(J2-Pad46)") (class "Default")
      (node (ref "J2") (pin "46") (pinfunction "46_46") (pintype "bidirectional+no_connect"))
    )
    (net (code "176") (name "unconnected-(J2-Pad47)") (class "Default")
      (node (ref "J2") (pin "47") (pinfunction "47_47") (pintype "bidirectional+no_connect"))
    )
    (net (code "177") (name "unconnected-(J2-Pad48)") (class "Default")
      (node (ref "J2") (pin "48") (pinfunction "48_48") (pintype "bidirectional+no_connect"))
    )
    (net (code "178") (name "unconnected-(J2-Pad49)") (class "Default")
      (node (ref "J2") (pin "49") (pinfunction "49_49") (pintype "bidirectional+no_connect"))
    )
    (net (code "179") (name "unconnected-(J2-Pad50)") (class "Default")
      (node (ref "J2") (pin "50") (pinfunction "50_50") (pintype "bidirectional+no_connect"))
    )
    (net (code "180") (name "unconnected-(J2-Pad51)") (class "Default")
      (node (ref "J2") (pin "51") (pinfunction "51_51") (pintype "bidirectional+no_connect"))
    )
    (net (code "181") (name "unconnected-(J2-Pad52)") (class "Default")
      (node (ref "J2") (pin "52") (pinfunction "52_52") (pintype "bidirectional+no_connect"))
    )
    (net (code "182") (name "unconnected-(J2-Pad53)") (class "Default")
      (node (ref "J2") (pin "53") (pinfunction "53_53") (pintype "bidirectional+no_connect"))
    )
    (net (code "183") (name "unconnected-(J2-Pad54)") (class "Default")
      (node (ref "J2") (pin "54") (pinfunction "54_54") (pintype "bidirectional+no_connect"))
    )
    (net (code "184") (name "unconnected-(J2-Pad55)") (class "Default")
      (node (ref "J2") (pin "55") (pinfunction "55_55") (pintype "bidirectional+no_connect"))
    )
    (net (code "185") (name "unconnected-(J2-Pad56)") (class "Default")
      (node (ref "J2") (pin "56") (pinfunction "56_56") (pintype "bidirectional+no_connect"))
    )
    (net (code "186") (name "unconnected-(J2-Pad57)") (class "Default")
      (node (ref "J2") (pin "57") (pinfunction "57_57") (pintype "bidirectional+no_connect"))
    )
    (net (code "187") (name "unconnected-(J2-Pad58)") (class "Default")
      (node (ref "J2") (pin "58") (pinfunction "58_58") (pintype "bidirectional+no_connect"))
    )
    (net (code "188") (name "unconnected-(J2-Pad59)") (class "Default")
      (node (ref "J2") (pin "59") (pinfunction "59_59") (pintype "bidirectional+no_connect"))
    )
    (net (code "189") (name "unconnected-(J2-Pad60)") (class "Default")
      (node (ref "J2") (pin "60") (pinfunction "60_60") (pintype "bidirectional+no_connect"))
    )
    (net (code "190") (name "unconnected-(J2-Pad61)") (class "Default")
      (node (ref "J2") (pin "61") (pinfunction "61_61") (pintype "bidirectional+no_connect"))
    )
    (net (code "191") (name "unconnected-(J2-Pad62)") (class "Default")
      (node (ref "J2") (pin "62") (pinfunction "62_62") (pintype "bidirectional+no_connect"))
    )
    (net (code "192") (name "unconnected-(J2-Pad63)") (class "Default")
      (node (ref "J2") (pin "63") (pinfunction "63_63") (pintype "bidirectional+no_connect"))
    )
    (net (code "193") (name "unconnected-(J2-Pad64)") (class "Default")
      (node (ref "J2") (pin "64") (pinfunction "64_64") (pintype "bidirectional+no_connect"))
    )
    (net (code "194") (name "unconnected-(J2-Pad65)") (class "Default")
      (node (ref "J2") (pin "65") (pinfunction "65_65") (pintype "bidirectional+no_connect"))
    )
    (net (code "195") (name "unconnected-(J2-Pad66)") (class "Default")
      (node (ref "J2") (pin "66") (pinfunction "66_66") (pintype "bidirectional+no_connect"))
    )
    (net (code "196") (name "unconnected-(J2-Pad67)") (class "Default")
      (node (ref "J2") (pin "67") (pinfunction "67_67") (pintype "bidirectional+no_connect"))
    )
    (net (code "197") (name "unconnected-(J2-Pad68)") (class "Default")
      (node (ref "J2") (pin "68") (pinfunction "68_68") (pintype "bidirectional+no_connect"))
    )
    (net (code "198") (name "unconnected-(J2-Pad69)") (class "Default")
      (node (ref "J2") (pin "69") (pinfunction "69_69") (pintype "bidirectional+no_connect"))
    )
    (net (code "199") (name "unconnected-(J2-Pad70)") (class "Default")
      (node (ref "J2") (pin "70") (pinfunction "70_70") (pintype "bidirectional+no_connect"))
    )
    (net (code "200") (name "unconnected-(J2-Pad71)") (class "Default")
      (node (ref "J2") (pin "71") (pinfunction "71_71") (pintype "bidirectional+no_connect"))
    )
    (net (code "201") (name "unconnected-(J2-Pad72)") (class "Default")
      (node (ref "J2") (pin "72") (pinfunction "72_72") (pintype "bidirectional+no_connect"))
    )
    (net (code "202") (name "unconnected-(J2-Pad73)") (class "Default")
      (node (ref "J2") (pin "73") (pinfunction "73_73") (pintype "bidirectional+no_connect"))
    )
    (net (code "203") (name "unconnected-(J2-Pad74)") (class "Default")
      (node (ref "J2") (pin "74") (pinfunction "74_74") (pintype "bidirectional+no_connect"))
    )
    (net (code "204") (name "unconnected-(J2-Pad75)") (class "Default")
      (node (ref "J2") (pin "75") (pinfunction "75_75") (pintype "bidirectional+no_connect"))
    )
    (net (code "205") (name "unconnected-(J2-Pad76)") (class "Default")
      (node (ref "J2") (pin "76") (pinfunction "76_76") (pintype "bidirectional+no_connect"))
    )
    (net (code "206") (name "unconnected-(J2-Pad77)") (class "Default")
      (node (ref "J2") (pin "77") (pinfunction "77_77") (pintype "bidirectional+no_connect"))
    )
    (net (code "207") (name "unconnected-(J2-Pad78)") (class "Default")
      (node (ref "J2") (pin "78") (pinfunction "78_78") (pintype "bidirectional+no_connect"))
    )
    (net (code "208") (name "unconnected-(J2-Pad79)") (class "Default")
      (node (ref "J2") (pin "79") (pinfunction "79_79") (pintype "bidirectional+no_connect"))
    )
    (net (code "209") (name "unconnected-(J2-Pad80)") (class "Default")
      (node (ref "J2") (pin "80") (pinfunction "80_80") (pintype "bidirectional+no_connect"))
    )
    (net (code "210") (name "unconnected-(J2-Pad81)") (class "Default")
      (node (ref "J2") (pin "81") (pinfunction "81_81") (pintype "bidirectional+no_connect"))
    )
    (net (code "211") (name "unconnected-(J2-Pad82)") (class "Default")
      (node (ref "J2") (pin "82") (pinfunction "82_82") (pintype "bidirectional+no_connect"))
    )
    (net (code "212") (name "unconnected-(J2-Pad83)") (class "Default")
      (node (ref "J2") (pin "83") (pinfunction "83_83") (pintype "bidirectional+no_connect"))
    )
    (net (code "213") (name "unconnected-(J2-Pad84)") (class "Default")
      (node (ref "J2") (pin "84") (pinfunction "84_84") (pintype "bidirectional+no_connect"))
    )
    (net (code "214") (name "unconnected-(J2-Pad85)") (class "Default")
      (node (ref "J2") (pin "85") (pinfunction "85_85") (pintype "bidirectional+no_connect"))
    )
    (net (code "215") (name "unconnected-(J2-Pad86)") (class "Default")
      (node (ref "J2") (pin "86") (pinfunction "86_86") (pintype "bidirectional+no_connect"))
    )
    (net (code "216") (name "unconnected-(J2-Pad87)") (class "Default")
      (node (ref "J2") (pin "87") (pinfunction "87_87") (pintype "bidirectional+no_connect"))
    )
    (net (code "217") (name "unconnected-(J2-Pad88)") (class "Default")
      (node (ref "J2") (pin "88") (pinfunction "88_88") (pintype "bidirectional+no_connect"))
    )
    (net (code "218") (name "unconnected-(J2-Pad89)") (class "Default")
      (node (ref "J2") (pin "89") (pinfunction "89_89") (pintype "bidirectional+no_connect"))
    )
    (net (code "219") (name "unconnected-(J2-Pad90)") (class "Default")
      (node (ref "J2") (pin "90") (pinfunction "90_90") (pintype "bidirectional+no_connect"))
    )
    (net (code "220") (name "unconnected-(J2-Pad91)") (class "Default")
      (node (ref "J2") (pin "91") (pinfunction "91_91") (pintype "bidirectional+no_connect"))
    )
    (net (code "221") (name "unconnected-(J2-Pad92)") (class "Default")
      (node (ref "J2") (pin "92") (pinfunction "92_92") (pintype "bidirectional+no_connect"))
    )
    (net (code "222") (name "unconnected-(J2-Pad93)") (class "Default")
      (node (ref "J2") (pin "93") (pinfunction "93_93") (pintype "bidirectional+no_connect"))
    )
    (net (code "223") (name "unconnected-(J2-Pad94)") (class "Default")
      (node (ref "J2") (pin "94") (pinfunction "94_94") (pintype "bidirectional+no_connect"))
    )
    (net (code "224") (name "unconnected-(J2-Pad95)") (class "Default")
      (node (ref "J2") (pin "95") (pinfunction "95_95") (pintype "bidirectional+no_connect"))
    )
    (net (code "225") (name "unconnected-(J2-Pad96)") (class "Default")
      (node (ref "J2") (pin "96") (pinfunction "96_96") (pintype "bidirectional+no_connect"))
    )
    (net (code "226") (name "unconnected-(J2-Pad97)") (class "Default")
      (node (ref "J2") (pin "97") (pinfunction "97_97") (pintype "bidirectional+no_connect"))
    )
    (net (code "227") (name "unconnected-(J2-Pad98)") (class "Default")
      (node (ref "J2") (pin "98") (pinfunction "98_98") (pintype "bidirectional+no_connect"))
    )
    (net (code "228") (name "unconnected-(J2-Pad99)") (class "Default")
      (node (ref "J2") (pin "99") (pinfunction "99_99") (pintype "bidirectional+no_connect"))
    )
    (net (code "229") (name "unconnected-(J2-Pad100)") (class "Default")
      (node (ref "J2") (pin "100") (pinfunction "100_100") (pintype "bidirectional+no_connect"))
    )
    (net (code "230") (name "unconnected-(SW1-Pad3)") (class "Default")
      (node (ref "SW1") (pin "3") (pinfunction "3_3") (pintype "unspecified+no_connect"))
    )
    (net (code "231") (name "unconnected-(U2-Pad13)") (class "Default")
      (node (ref "U2") (pin "13") (pinfunction "13_13") (pintype "unspecified+no_connect"))
    )
    (net (code "232") (name "unconnected-(U2-Pad14)") (class "Default")
      (node (ref "U2") (pin "14") (pinfunction "14_14") (pintype "unspecified+no_connect"))
    )
    (net (code "233") (name "unconnected-(U2-Pad15)") (class "Default")
      (node (ref "U2") (pin "15") (pinfunction "15_15") (pintype "unspecified+no_connect"))
    )
    (net (code "234") (name "unconnected-(U2-Pad16)") (class "Default")
      (node (ref "U2") (pin "16") (pinfunction "16_16") (pintype "unspecified+no_connect"))
    )
    (net (code "235") (name "unconnected-(U3-HSIN-Pad39)") (class "Default")
      (node (ref "U3") (pin "39") (pinfunction "HSIN_39") (pintype "unspecified+no_connect"))
    )
    (net (code "236") (name "unconnected-(U3-HSIP-Pad38)") (class "Default")
      (node (ref "U3") (pin "38") (pinfunction "HSIP_38") (pintype "unspecified+no_connect"))
    )
    (net (code "237") (name "unconnected-(U3-HSON-Pad35)") (class "Default")
      (node (ref "U3") (pin "35") (pinfunction "HSON_35") (pintype "unspecified+no_connect"))
    )
    (net (code "238") (name "unconnected-(U3-HSOP-Pad36)") (class "Default")
      (node (ref "U3") (pin "36") (pinfunction "HSOP_36") (pintype "unspecified+no_connect"))
    )
    (net (code "239") (name "unconnected-(U3-INTERRUPT{slash}GPIO57-Pad19)") (class "Default")
      (node (ref "U3") (pin "19") (pinfunction "INTERRUPT/GPIO57_19") (pintype "unspecified+no_connect"))
    )
    (net (code "240") (name "unconnected-(U3-LAN2LED1{slash}GPIO46-Pad77)") (class "Default")
      (node (ref "U3") (pin "77") (pinfunction "LAN2LED1/GPIO46_77") (pintype "unspecified+no_connect"))
    )
    (net (code "241") (name "unconnected-(U3-LAN3LED1{slash}GPIO41-Pad72)") (class "Default")
      (node (ref "U3") (pin "72") (pinfunction "LAN3LED1/GPIO41_72") (pintype "unspecified+no_connect"))
    )
    (net (code "242") (name "unconnected-(U3-LAN4LED1{slash}GPIO40-Pad71)") (class "Default")
      (node (ref "U3") (pin "71") (pinfunction "LAN4LED1/GPIO40_71") (pintype "unspecified+no_connect"))
    )
    (net (code "243") (name "unconnected-(U3-M2P_RXCLK{slash}M2M_TXCLK{slash}RG2_TXCLK{slash}GPIO06-Pad50)") (class "Default")
      (node (ref "U3") (pin "50") (pinfunction "M2P_RXCLK/M2M_TXCLK/RG2_TXCLK/GPIO06_50") (pintype "unspecified+no_connect"))
    )
    (net (code "244") (name "unconnected-(U3-M2P_RXD1{slash}M2M_TXD1{slash}RG2_TXD1{slash}GPIO03-Pad47)") (class "Default")
      (node (ref "U3") (pin "47") (pinfunction "M2P_RXD1/M2M_TXD1/RG2_TXD1/GPIO03_47") (pintype "unspecified+no_connect"))
    )
    (net (code "245") (name "unconnected-(U3-M2P_TXCLK{slash}M2M_RXCLK{slash}RG2_RXCLK{slash}GPIO07-Pad51)") (class "Default")
      (node (ref "U3") (pin "51") (pinfunction "M2P_TXCLK/M2M_RXCLK/RG2_RXCLK/GPIO07_51") (pintype "unspecified+no_connect"))
    )
    (net (code "246") (name "unconnected-(U3-M2P_TXD2{slash}M2M_RXD2{slash}RG2_RXD2{slash}GPIO11-Pad55)") (class "Default")
      (node (ref "U3") (pin "55") (pinfunction "M2P_TXD2/M2M_RXD2/RG2_RXD2/GPIO11_55") (pintype "unspecified+no_connect"))
    )
    (net (code "247") (name "unconnected-(U3-M2P_TXD3{slash}M2M_RXD3{slash}RG2_RXD3{slash}GPIO12-Pad56)") (class "Default")
      (node (ref "U3") (pin "56") (pinfunction "M2P_TXD3/M2M_RXD3/RG2_RXD3/GPIO12_56") (pintype "unspecified+no_connect"))
    )
    (net (code "248") (name "unconnected-(U3-M2P_TXEN{slash}M2M_RXDV{slash}RG2_RXCTL{slash}GPIO08-Pad52)") (class "Default")
      (node (ref "U3") (pin "52") (pinfunction "M2P_TXEN/M2M_RXDV/RG2_RXCTL/GPIO08_52") (pintype "unspecified+no_connect"))
    )
    (net (code "249") (name "unconnected-(U3-P3MDIAN-Pad3)") (class "Default")
      (node (ref "U3") (pin "3") (pinfunction "P3MDIAN_3") (pintype "unspecified+no_connect"))
    )
    (net (code "250") (name "unconnected-(U3-P3MDIAP-Pad2)") (class "Default")
      (node (ref "U3") (pin "2") (pinfunction "P3MDIAP_2") (pintype "unspecified+no_connect"))
    )
    (net (code "251") (name "unconnected-(U3-P3MDIBN-Pad5)") (class "Default")
      (node (ref "U3") (pin "5") (pinfunction "P3MDIBN_5") (pintype "unspecified+no_connect"))
    )
    (net (code "252") (name "unconnected-(U3-P3MDIBP-Pad4)") (class "Default")
      (node (ref "U3") (pin "4") (pinfunction "P3MDIBP_4") (pintype "unspecified+no_connect"))
    )
    (net (code "253") (name "unconnected-(U3-P3MDICN-Pad8)") (class "Default")
      (node (ref "U3") (pin "8") (pinfunction "P3MDICN_8") (pintype "unspecified+no_connect"))
    )
    (net (code "254") (name "unconnected-(U3-P3MDICP-Pad7)") (class "Default")
      (node (ref "U3") (pin "7") (pinfunction "P3MDICP_7") (pintype "unspecified+no_connect"))
    )
    (net (code "255") (name "unconnected-(U3-P3MDIDN-Pad10)") (class "Default")
      (node (ref "U3") (pin "10") (pinfunction "P3MDIDN_10") (pintype "unspecified+no_connect"))
    )
    (net (code "256") (name "unconnected-(U3-P3MDIDP-Pad9)") (class "Default")
      (node (ref "U3") (pin "9") (pinfunction "P3MDIDP_9") (pintype "unspecified+no_connect"))
    )
    (net (code "257") (name "unconnected-(U3-P4MDIAN-Pad23)") (class "Default")
      (node (ref "U3") (pin "23") (pinfunction "P4MDIAN_23") (pintype "unspecified+no_connect"))
    )
    (net (code "258") (name "unconnected-(U3-P4MDIAP-Pad22)") (class "Default")
      (node (ref "U3") (pin "22") (pinfunction "P4MDIAP_22") (pintype "unspecified+no_connect"))
    )
    (net (code "259") (name "unconnected-(U3-P4MDIBN-Pad26)") (class "Default")
      (node (ref "U3") (pin "26") (pinfunction "P4MDIBN_26") (pintype "unspecified+no_connect"))
    )
    (net (code "260") (name "unconnected-(U3-P4MDIBP-Pad25)") (class "Default")
      (node (ref "U3") (pin "25") (pinfunction "P4MDIBP_25") (pintype "unspecified+no_connect"))
    )
    (net (code "261") (name "unconnected-(U3-P4MDICN-Pad29)") (class "Default")
      (node (ref "U3") (pin "29") (pinfunction "P4MDICN_29") (pintype "unspecified+no_connect"))
    )
    (net (code "262") (name "unconnected-(U3-P4MDICP-Pad28)") (class "Default")
      (node (ref "U3") (pin "28") (pinfunction "P4MDICP_28") (pintype "unspecified+no_connect"))
    )
    (net (code "263") (name "unconnected-(U3-P4MDIDN-Pad31)") (class "Default")
      (node (ref "U3") (pin "31") (pinfunction "P4MDIDN_31") (pintype "unspecified+no_connect"))
    )
    (net (code "264") (name "unconnected-(U3-P4MDIDP-Pad30)") (class "Default")
      (node (ref "U3") (pin "30") (pinfunction "P4MDIDP_30") (pintype "unspecified+no_connect"))
    )
    (net (code "265") (name "unconnected-(U3-RTT1-Pad15)") (class "Default")
      (node (ref "U3") (pin "15") (pinfunction "RTT1_15") (pintype "unspecified+no_connect"))
    )
    (net (code "266") (name "unconnected-(U3-RTT2-Pad16)") (class "Default")
      (node (ref "U3") (pin "16") (pinfunction "RTT2_16") (pintype "unspecified+no_connect"))
    )
    (net (code "267") (name "unconnected-(U3-SDA{slash}GPIO55-Pad88)") (class "Default")
      (node (ref "U3") (pin "88") (pinfunction "SDA/GPIO55_88") (pintype "unspecified+no_connect"))
    )
    (net (code "268") (name "unconnected-(U3-SPIF_CLK{slash}M2P_RXD0{slash}M2M_TXD0{slash}RG2_TXD0{slash}GPIO04-Pad48)") (class "Default")
      (node (ref "U3") (pin "48") (pinfunction "SPIF_CLK/M2P_RXD0/M2M_TXD0/RG2_TXD0/GPIO04_48") (pintype "unspecified+no_connect"))
    )
    (net (code "269") (name "unconnected-(U3-SPIF_CS{slash}M2P_TXD1{slash}M2M_RXD1{slash}RG2_RXD1{slash}GPIO10-Pad54)") (class "Default")
      (node (ref "U3") (pin "54") (pinfunction "SPIF_CS/M2P_TXD1/M2M_RXD1/RG2_RXD1/GPIO10_54") (pintype "unspecified+no_connect"))
    )
    (net (code "270") (name "unconnected-(U3-SPIF_D0{slash}M2P_RXDV{slash}M2M_TXEN{slash}RG2_TXCTL{slash}GPIO05-Pad49)") (class "Default")
      (node (ref "U3") (pin "49") (pinfunction "SPIF_D0/M2P_RXDV/M2M_TXEN/RG2_TXCTL/GPIO05_49") (pintype "unspecified+no_connect"))
    )
    (net (code "271") (name "unconnected-(U3-SPIF_D1{slash}M2P_TXD0{slash}M2M_RXD0{slash}RG2_RXD0{slash}GPIO09-Pad53)") (class "Default")
      (node (ref "U3") (pin "53") (pinfunction "SPIF_D1/M2P_TXD0/M2M_RXD0/RG2_RXD0/GPIO09_53") (pintype "unspecified+no_connect"))
    )
    (net (code "272") (name "unconnected-(U3-UART_RX{slash}M2P_RXD3{slash}M2M_TXD3{slash}RG2_TXD3{slash}GPIO01-Pad45)") (class "Default")
      (node (ref "U3") (pin "45") (pinfunction "UART_RX/M2P_RXD3/M2M_TXD3/RG2_TXD3/GPIO01_45") (pintype "unspecified+no_connect"))
    )
    (net (code "273") (name "unconnected-(U3-UART_TX{slash}M2P_RXD2{slash}M2M_TXD2{slash}RG2_TXD2{slash}GPIO02-Pad46)") (class "Default")
      (node (ref "U3") (pin "46") (pinfunction "UART_TX/M2P_RXD2/M2M_TXD2/RG2_TXD2/GPIO02_46") (pintype "unspecified+no_connect"))
    )
    (net (code "274") (name "unconnected-(U6-CDB-Pad6)") (class "Default")
      (node (ref "U6") (pin "6") (pinfunction "CDB_6") (pintype "unspecified+no_connect"))
    )
    (net (code "275") (name "unconnected-(U6-T2P-Pad7)") (class "Default")
      (node (ref "U6") (pin "7") (pinfunction "T2P_7") (pintype "unspecified+no_connect"))
    )
    (net (code "276") (name "unconnected-(U12-NC-Pad4)") (class "Default")
      (node (ref "U12") (pin "4") (pinfunction "NC_4") (pintype "unspecified+no_connect"))
    )
    (net (code "277") (name "unconnected-(U12-ST-Pad5)") (class "Default")
      (node (ref "U12") (pin "5") (pinfunction "ST_5") (pintype "unspecified+no_connect"))
    )
    (net (code "278") (name "unconnected-(U13-NC-Pad4)") (class "Default")
      (node (ref "U13") (pin "4") (pinfunction "NC_4") (pintype "unspecified+no_connect"))
    )
    (net (code "279") (name "unconnected-(U13-ST-Pad5)") (class "Default")
      (node (ref "U13") (pin "5") (pinfunction "ST_5") (pintype "unspecified+no_connect"))
    )
    (net (code "280") (name "unconnected-(USBC1-SBU1-PadA8)") (class "Default")
      (node (ref "USBC1") (pin "A8") (pinfunction "SBU1_A8") (pintype "unspecified+no_connect"))
    )
    (net (code "281") (name "unconnected-(USBC1-SBU2-PadB8)") (class "Default")
      (node (ref "USBC1") (pin "B8") (pinfunction "SBU2_B8") (pintype "unspecified+no_connect"))
    )
  )
)
